# NeuroStimDuino.net
KiCad netlist of a schematic drawn in EAGLE
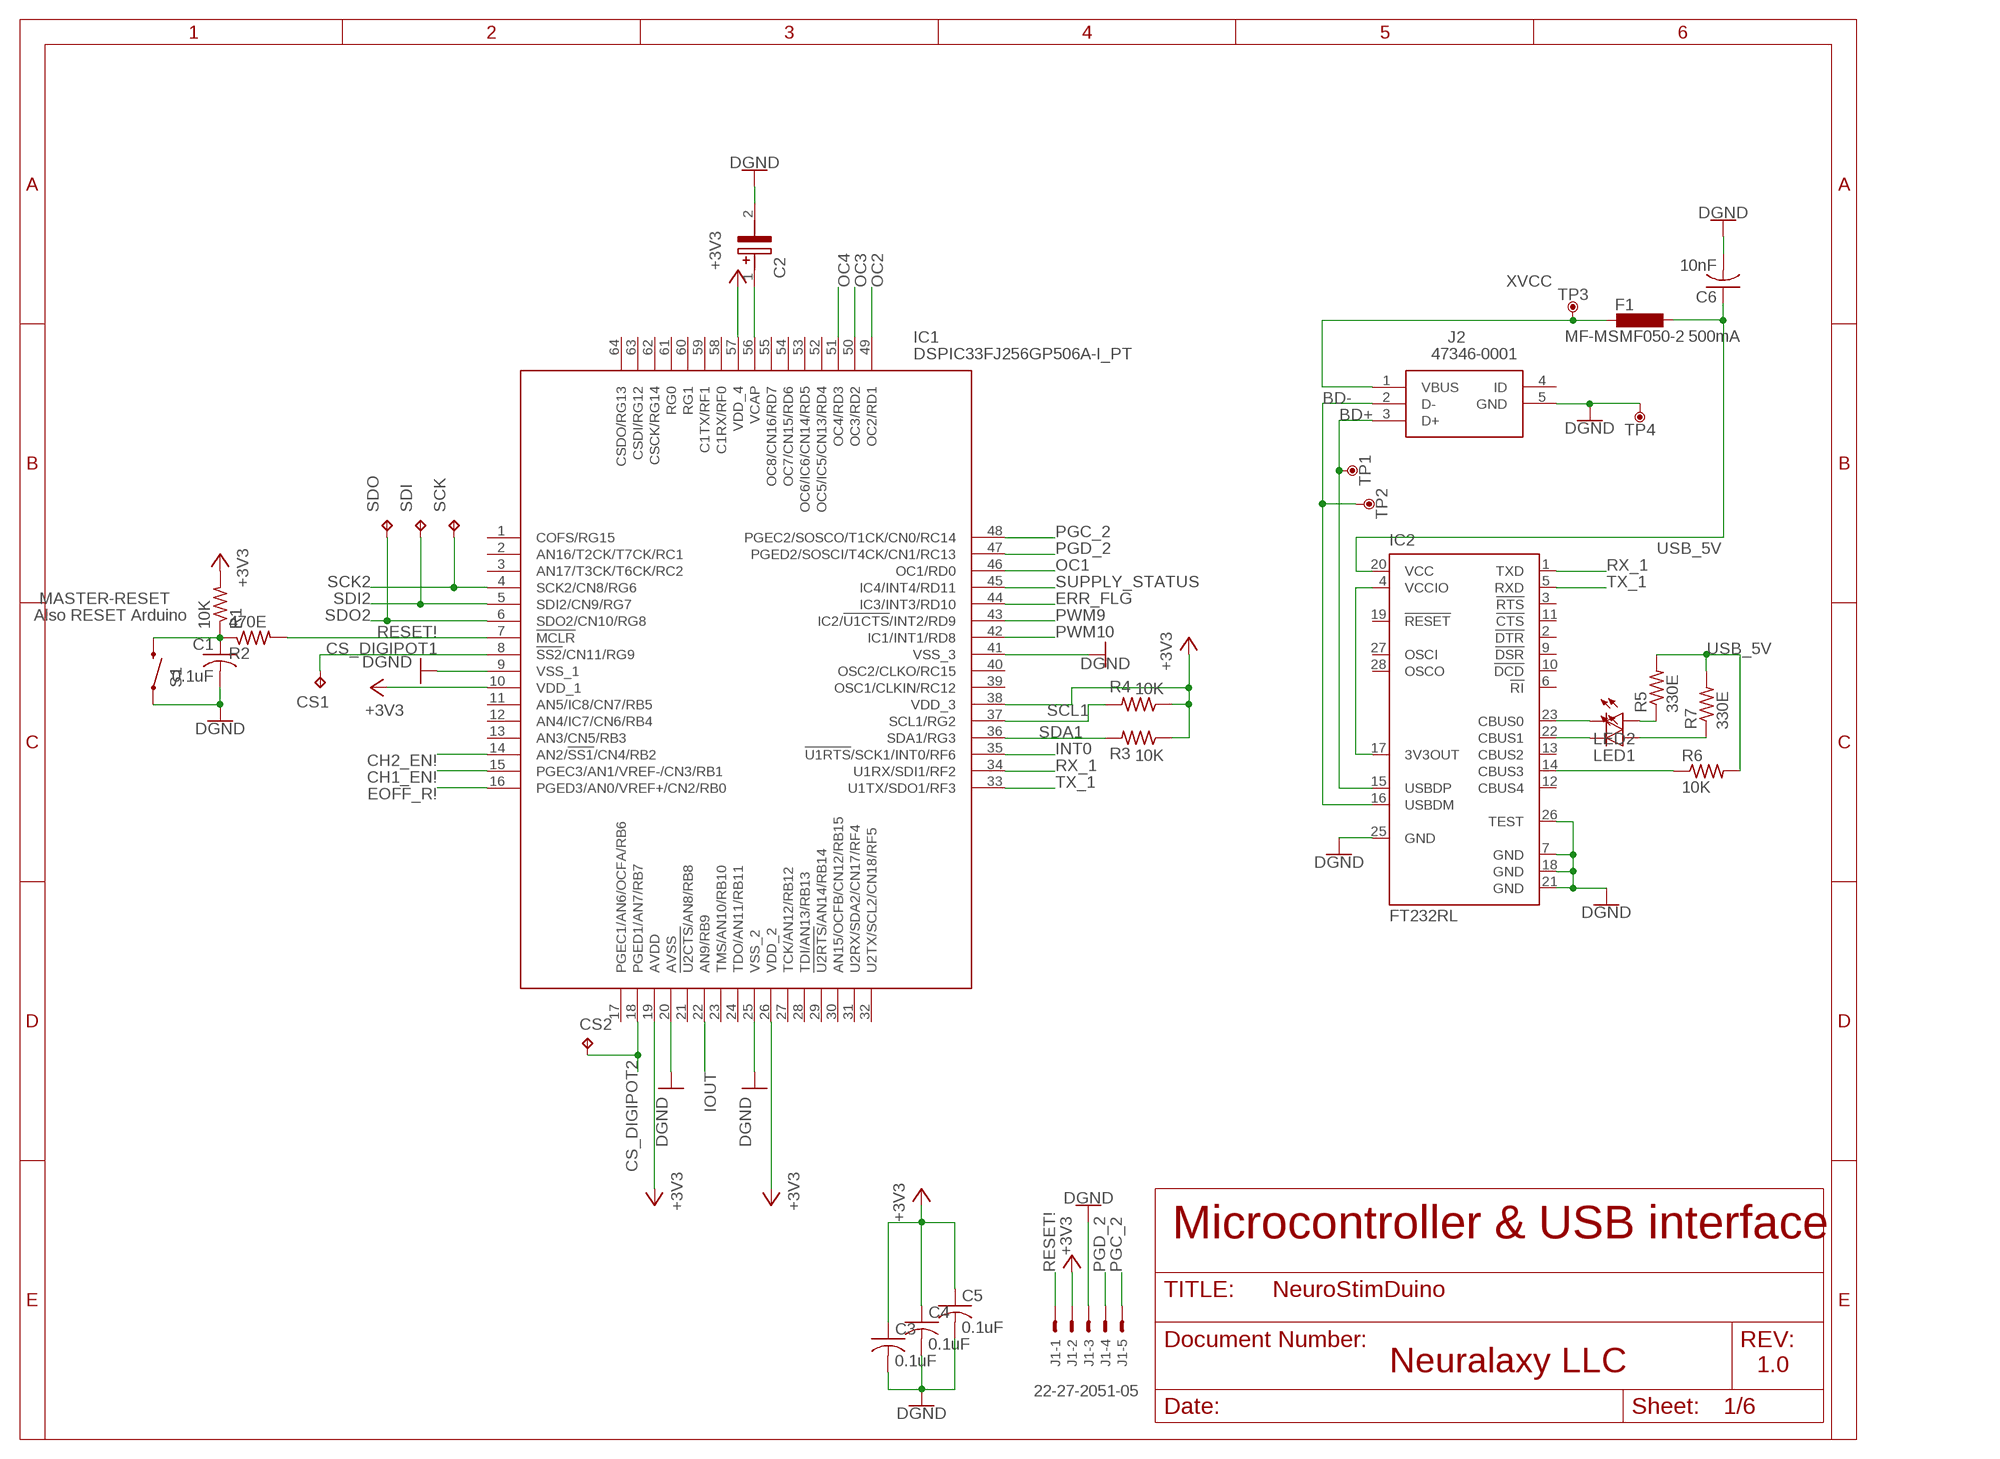
[diagram p0: schematic, sheet 1]
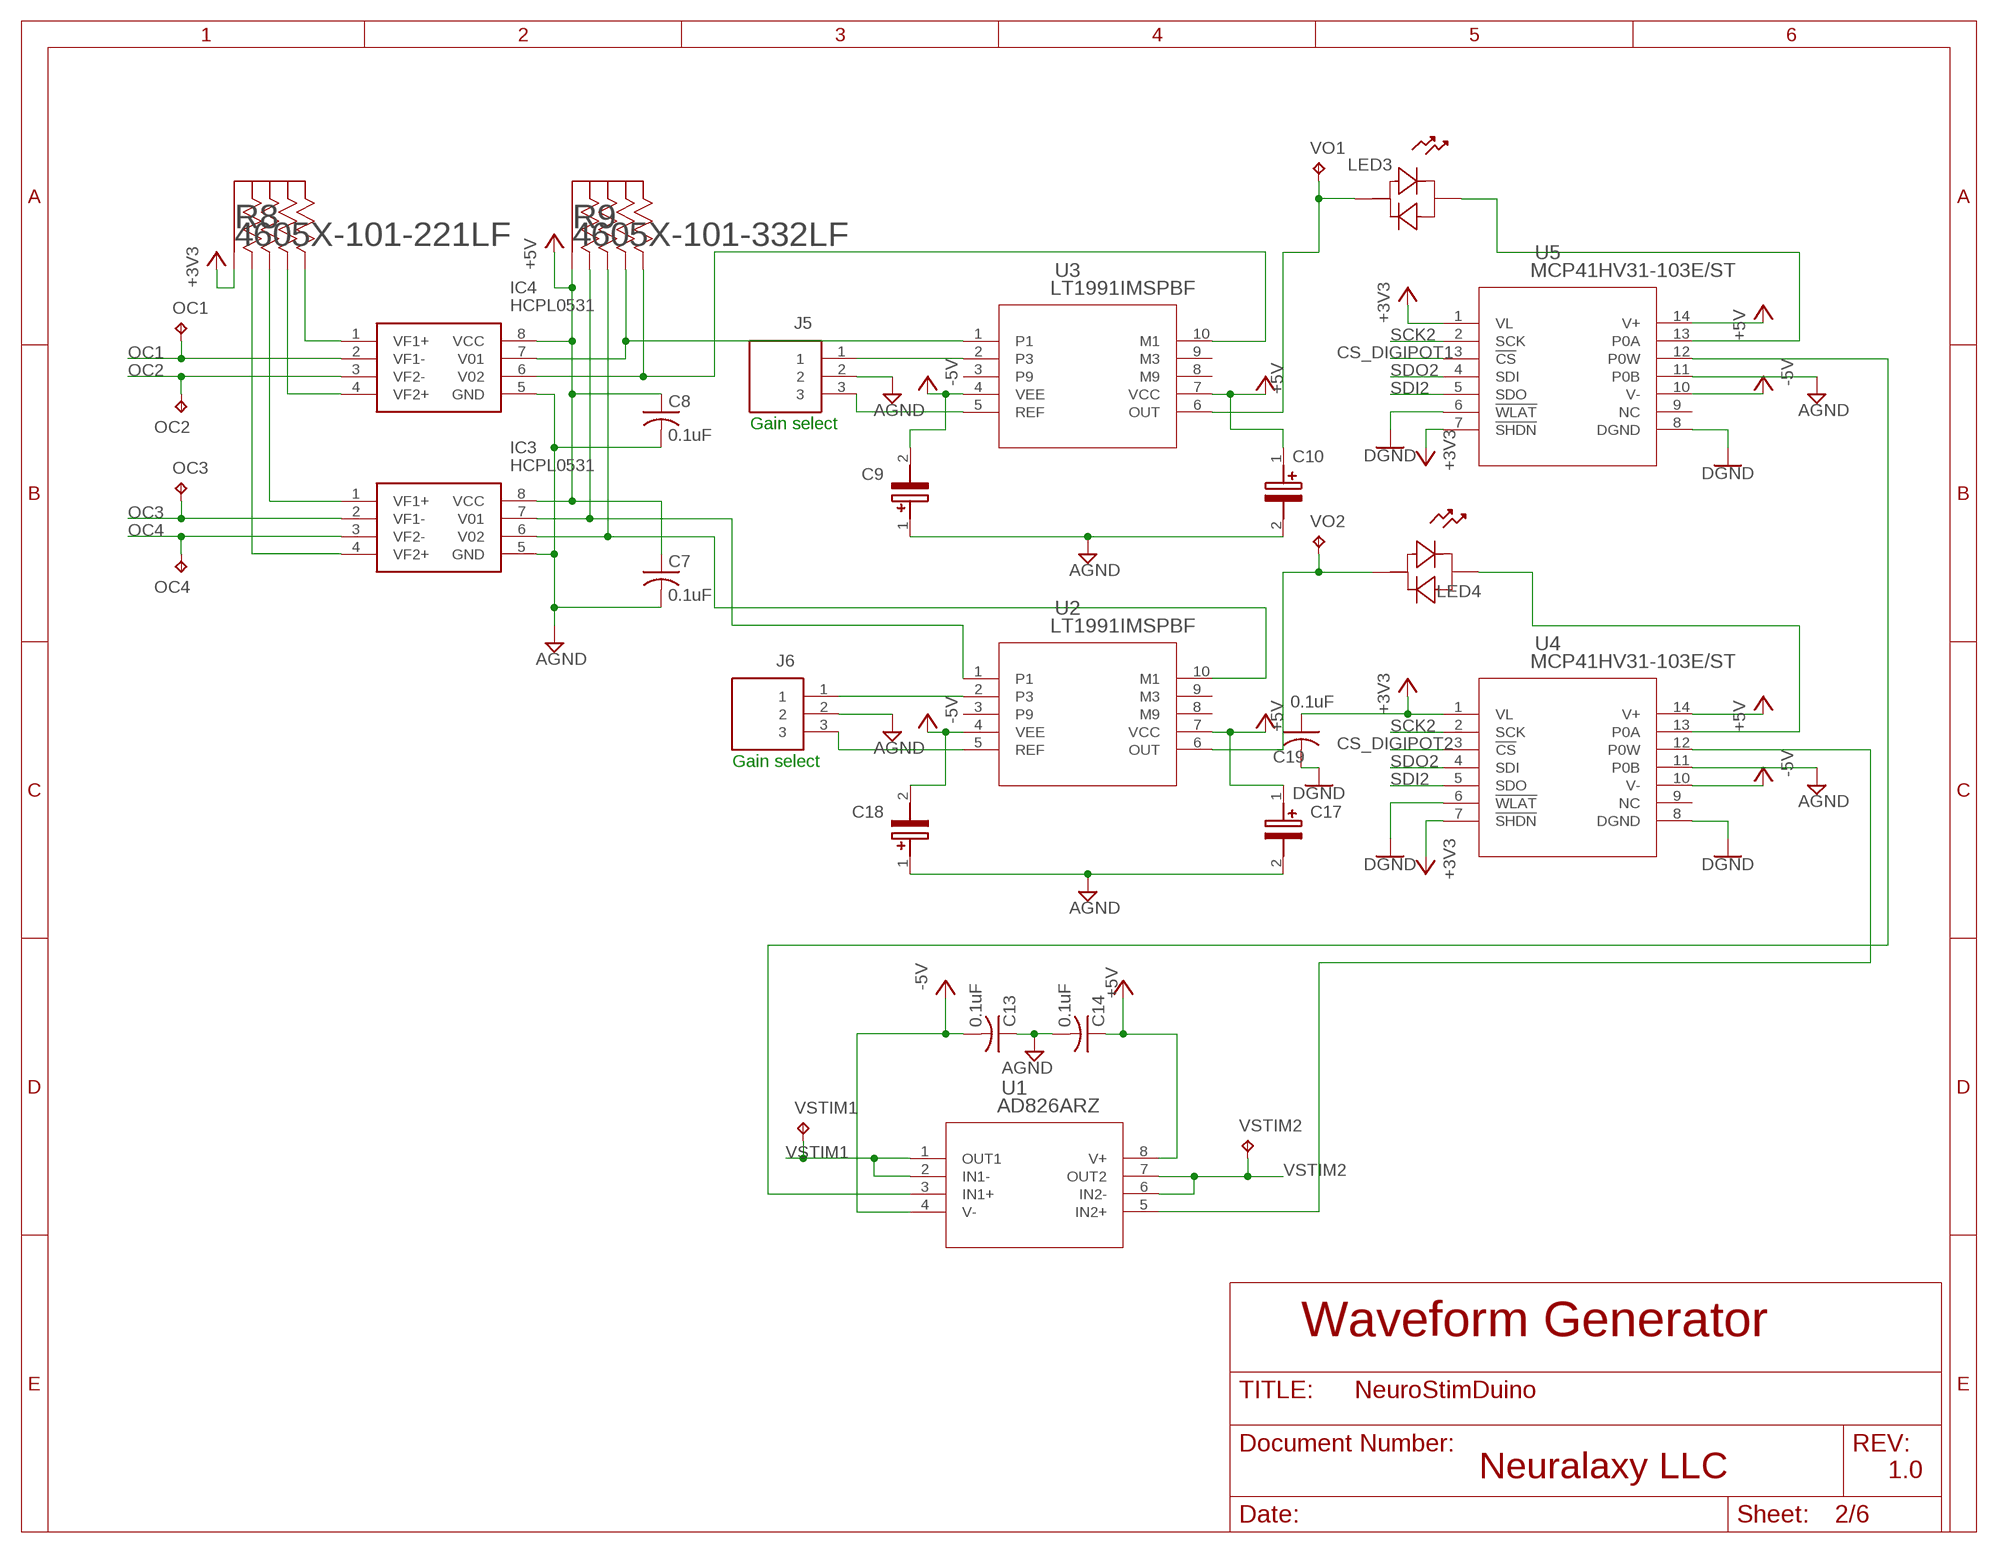
[diagram p1: schematic, sheet 2]
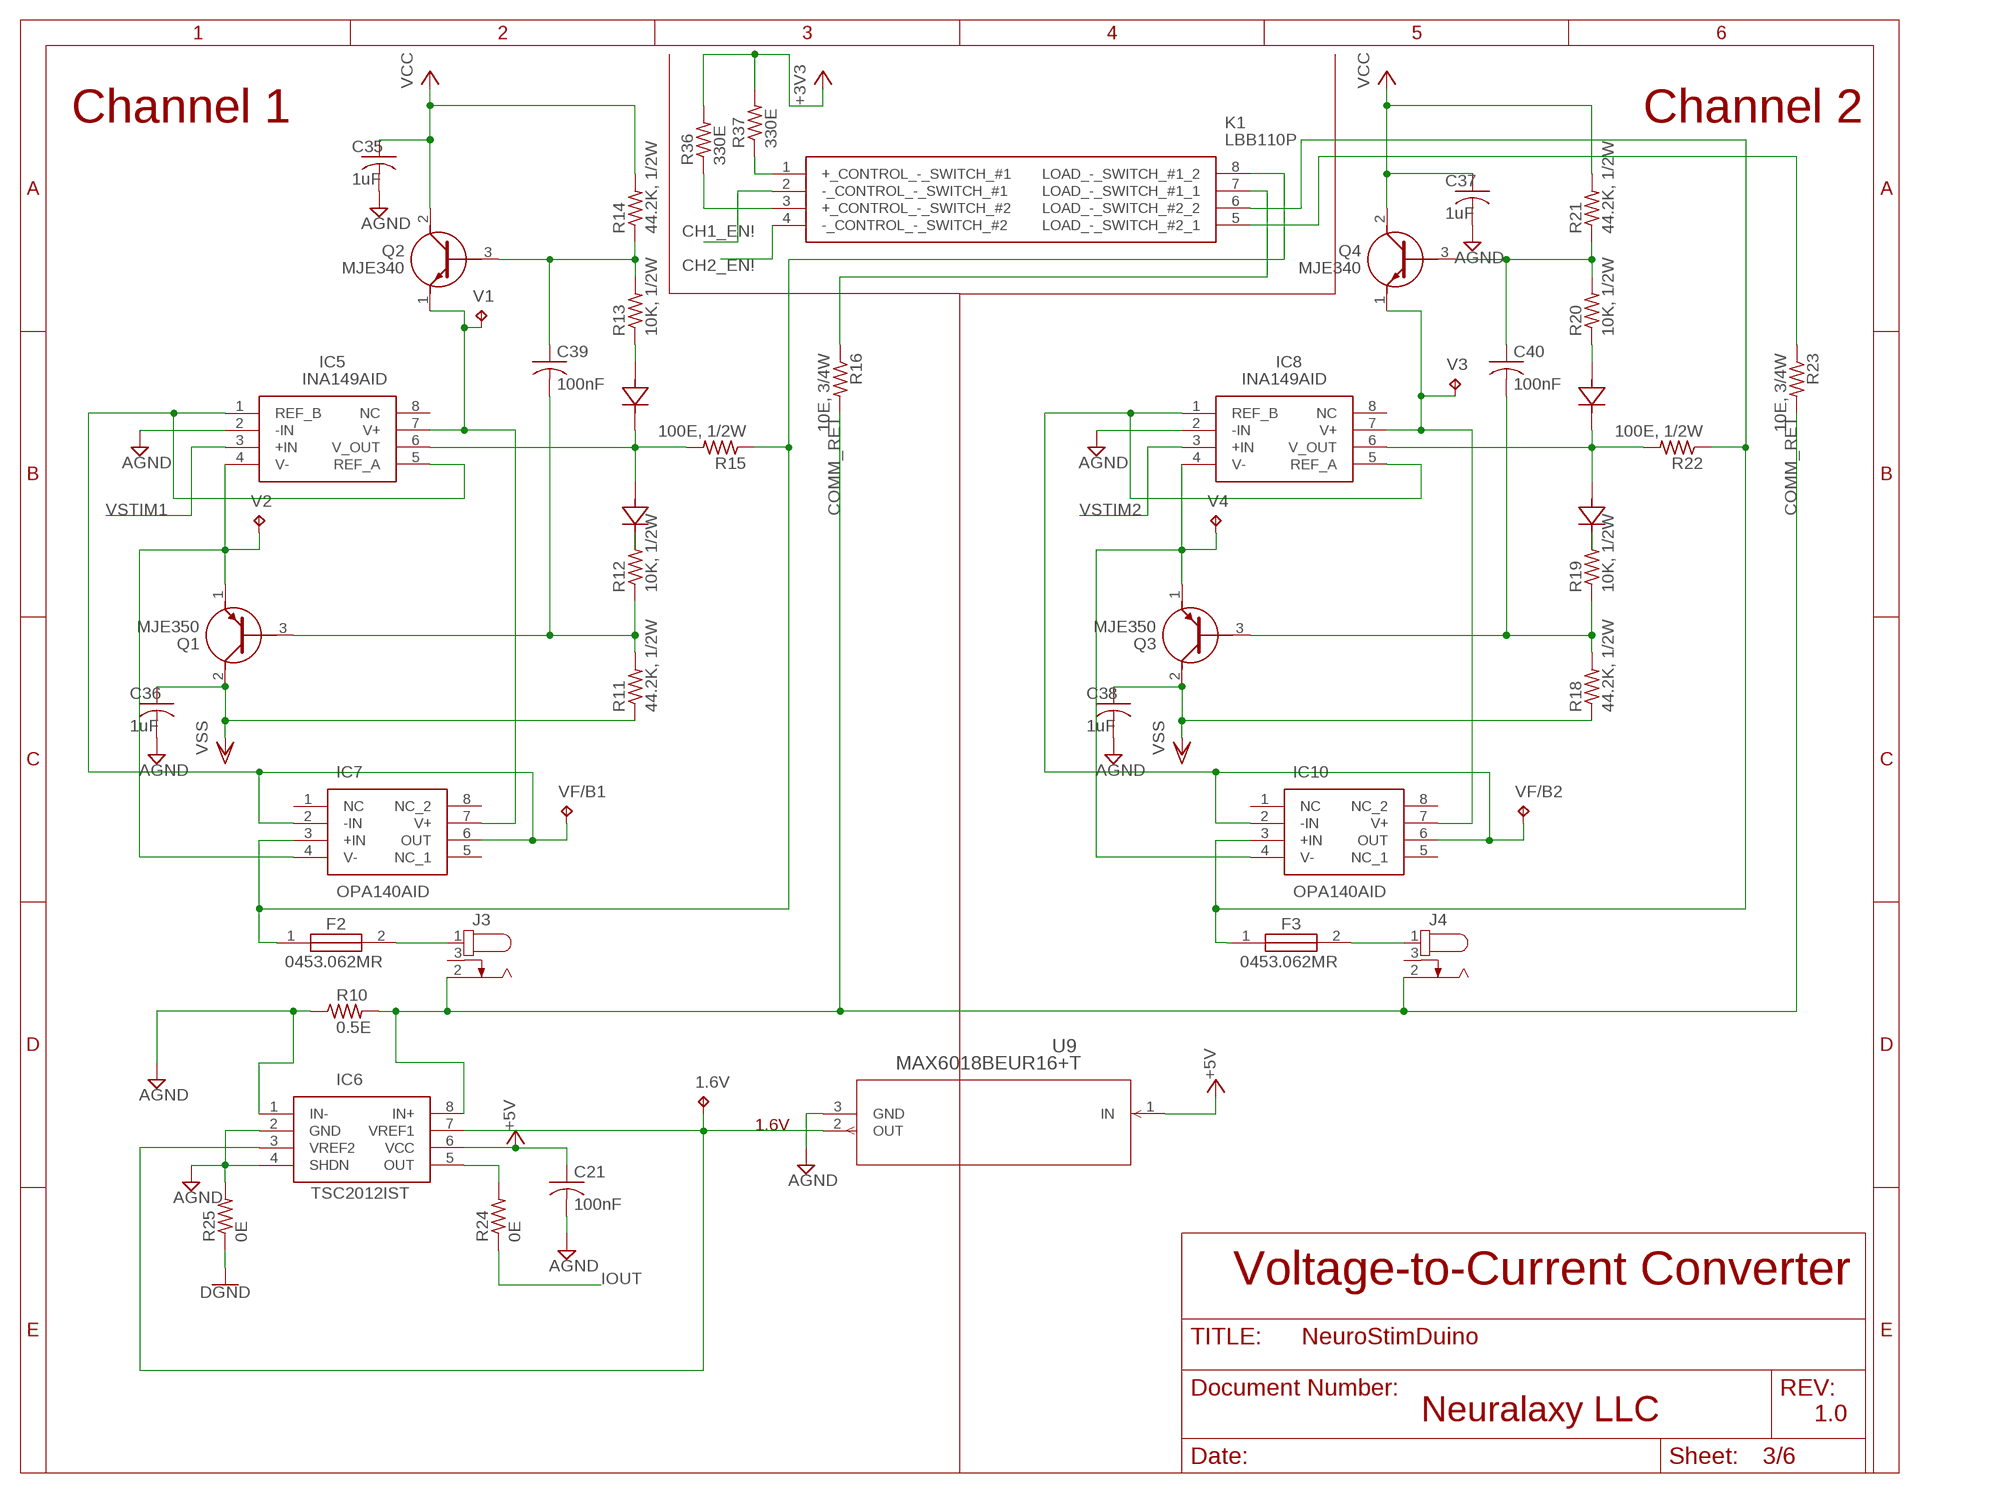
[diagram p2: schematic, sheet 3]
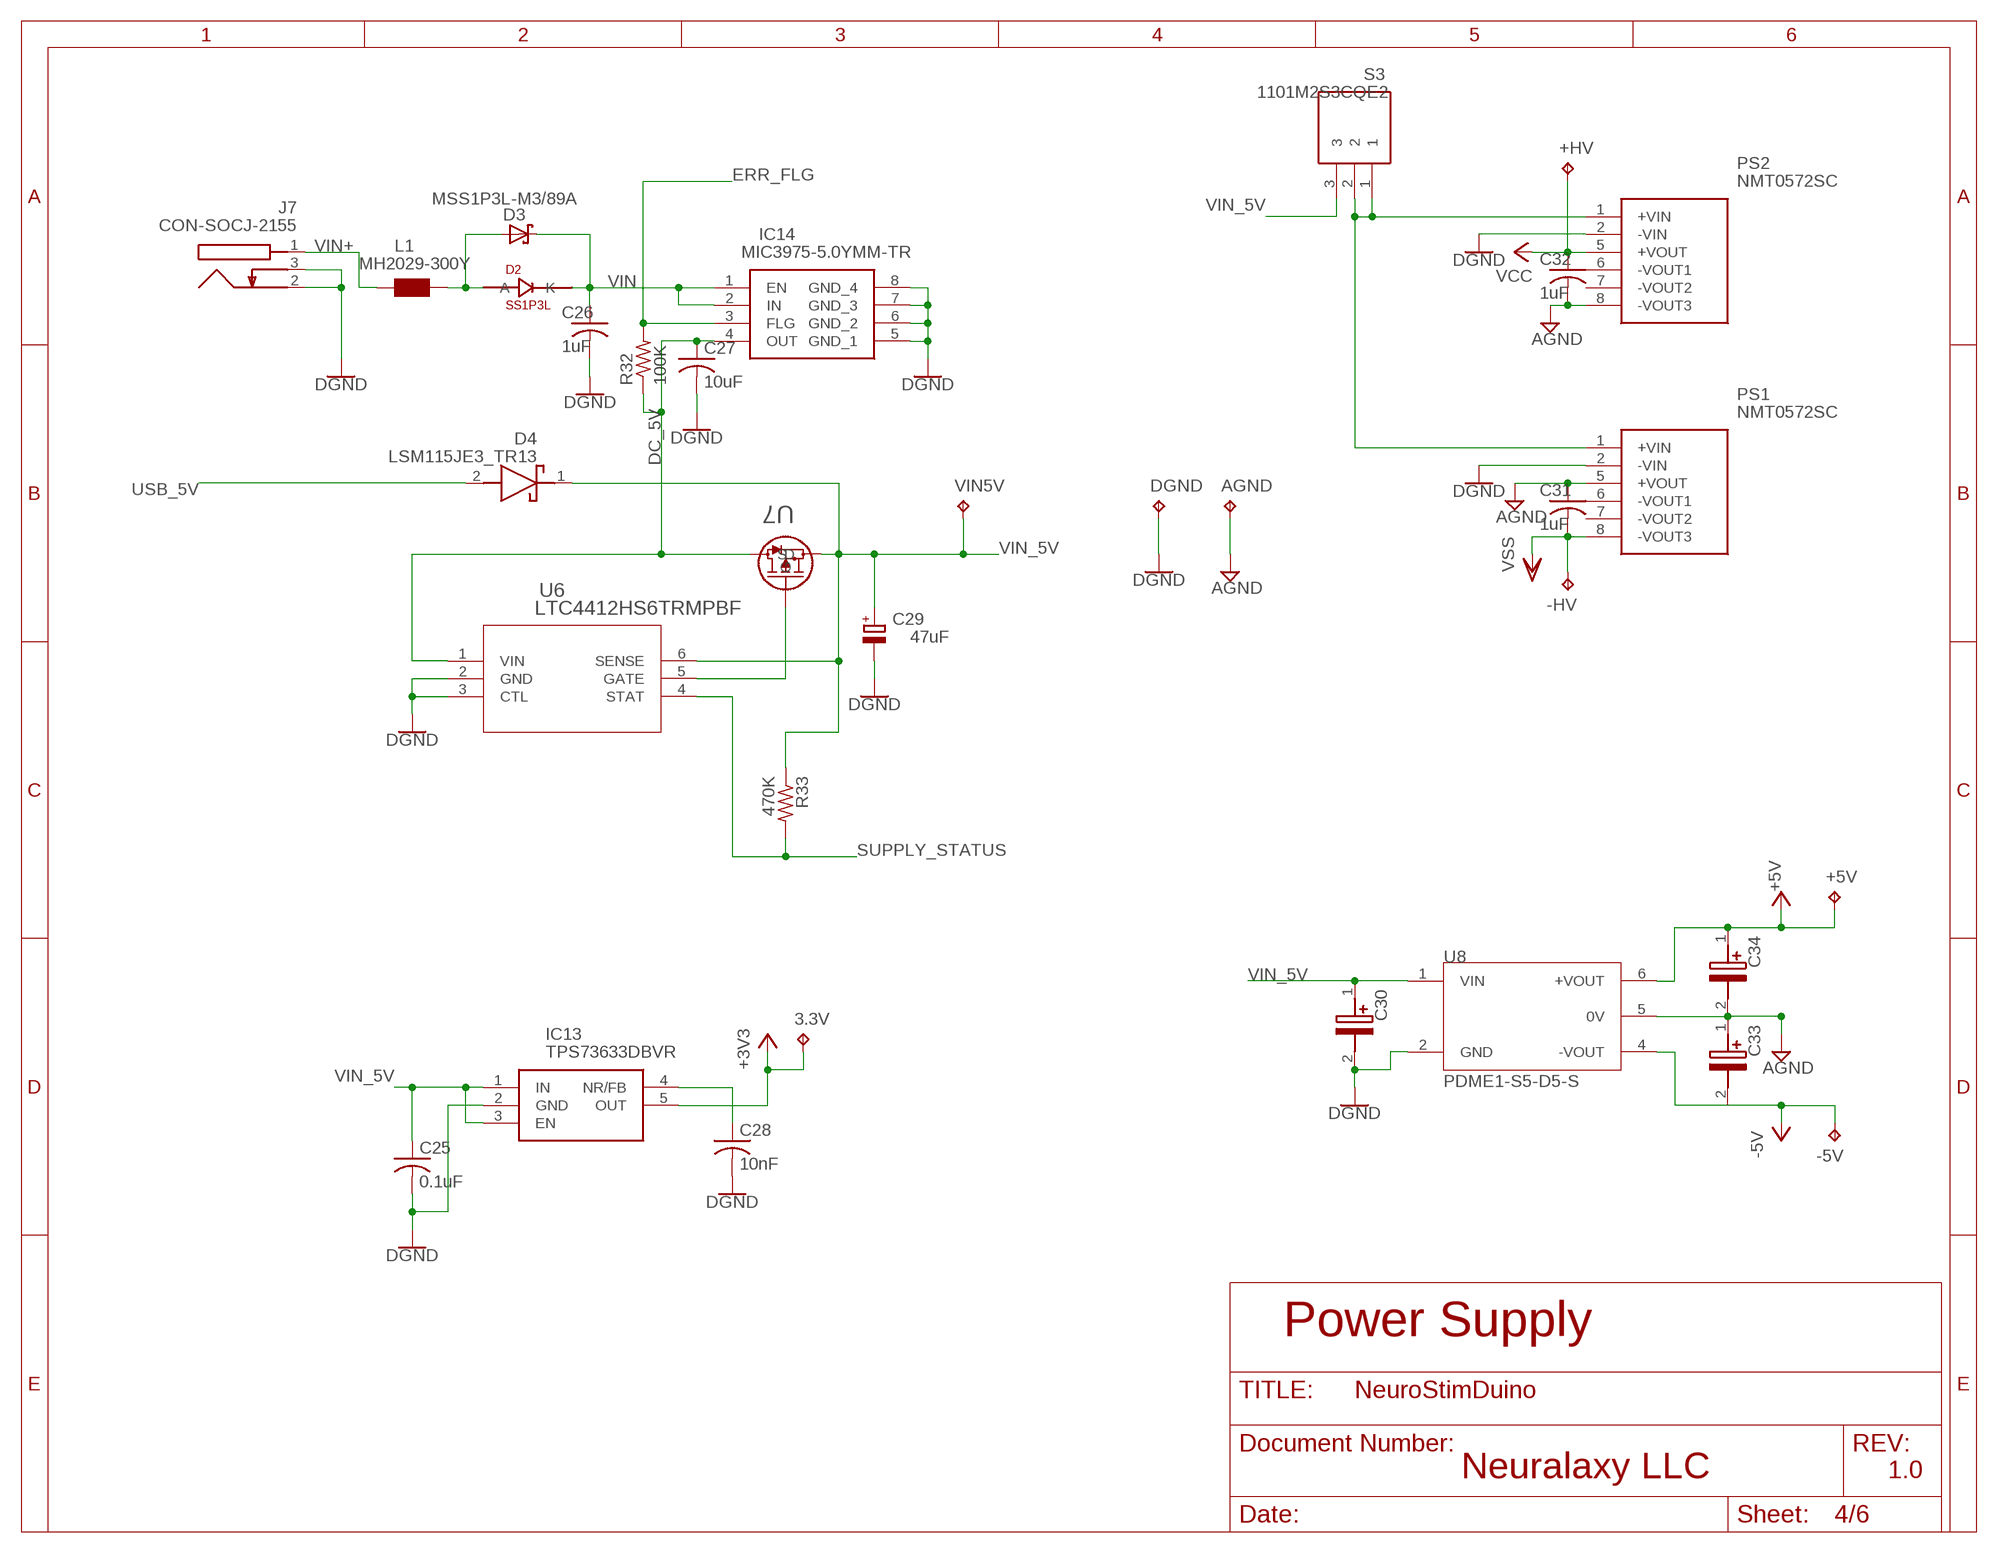
[diagram p3: schematic, sheet 4]
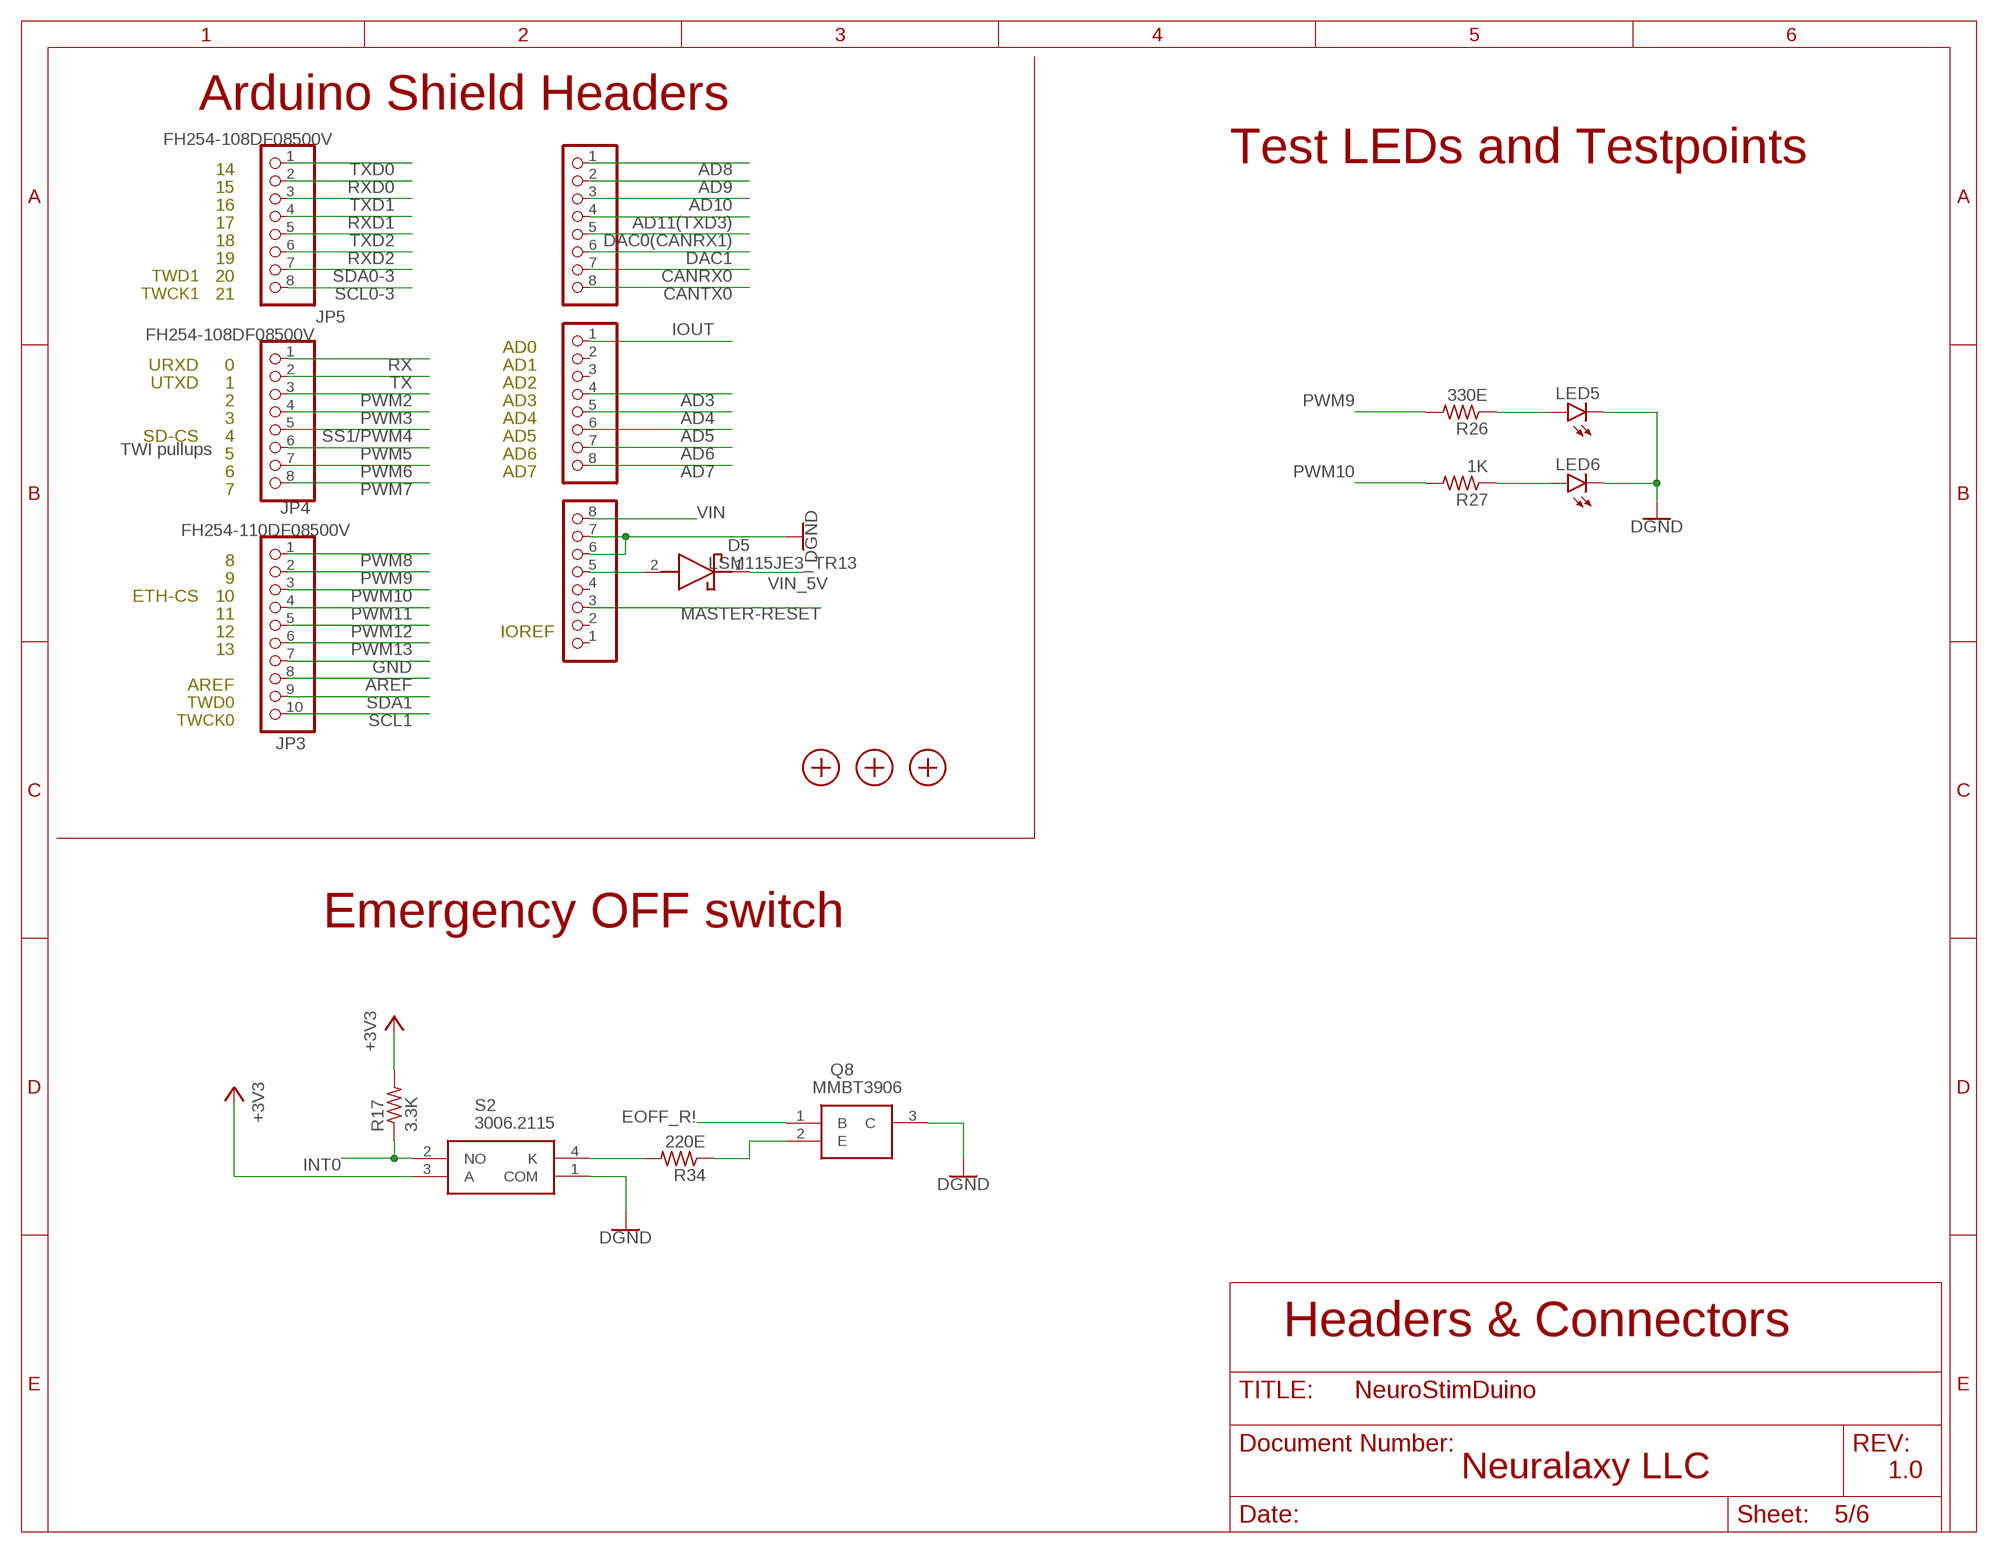
[diagram p4: schematic, sheet 5]
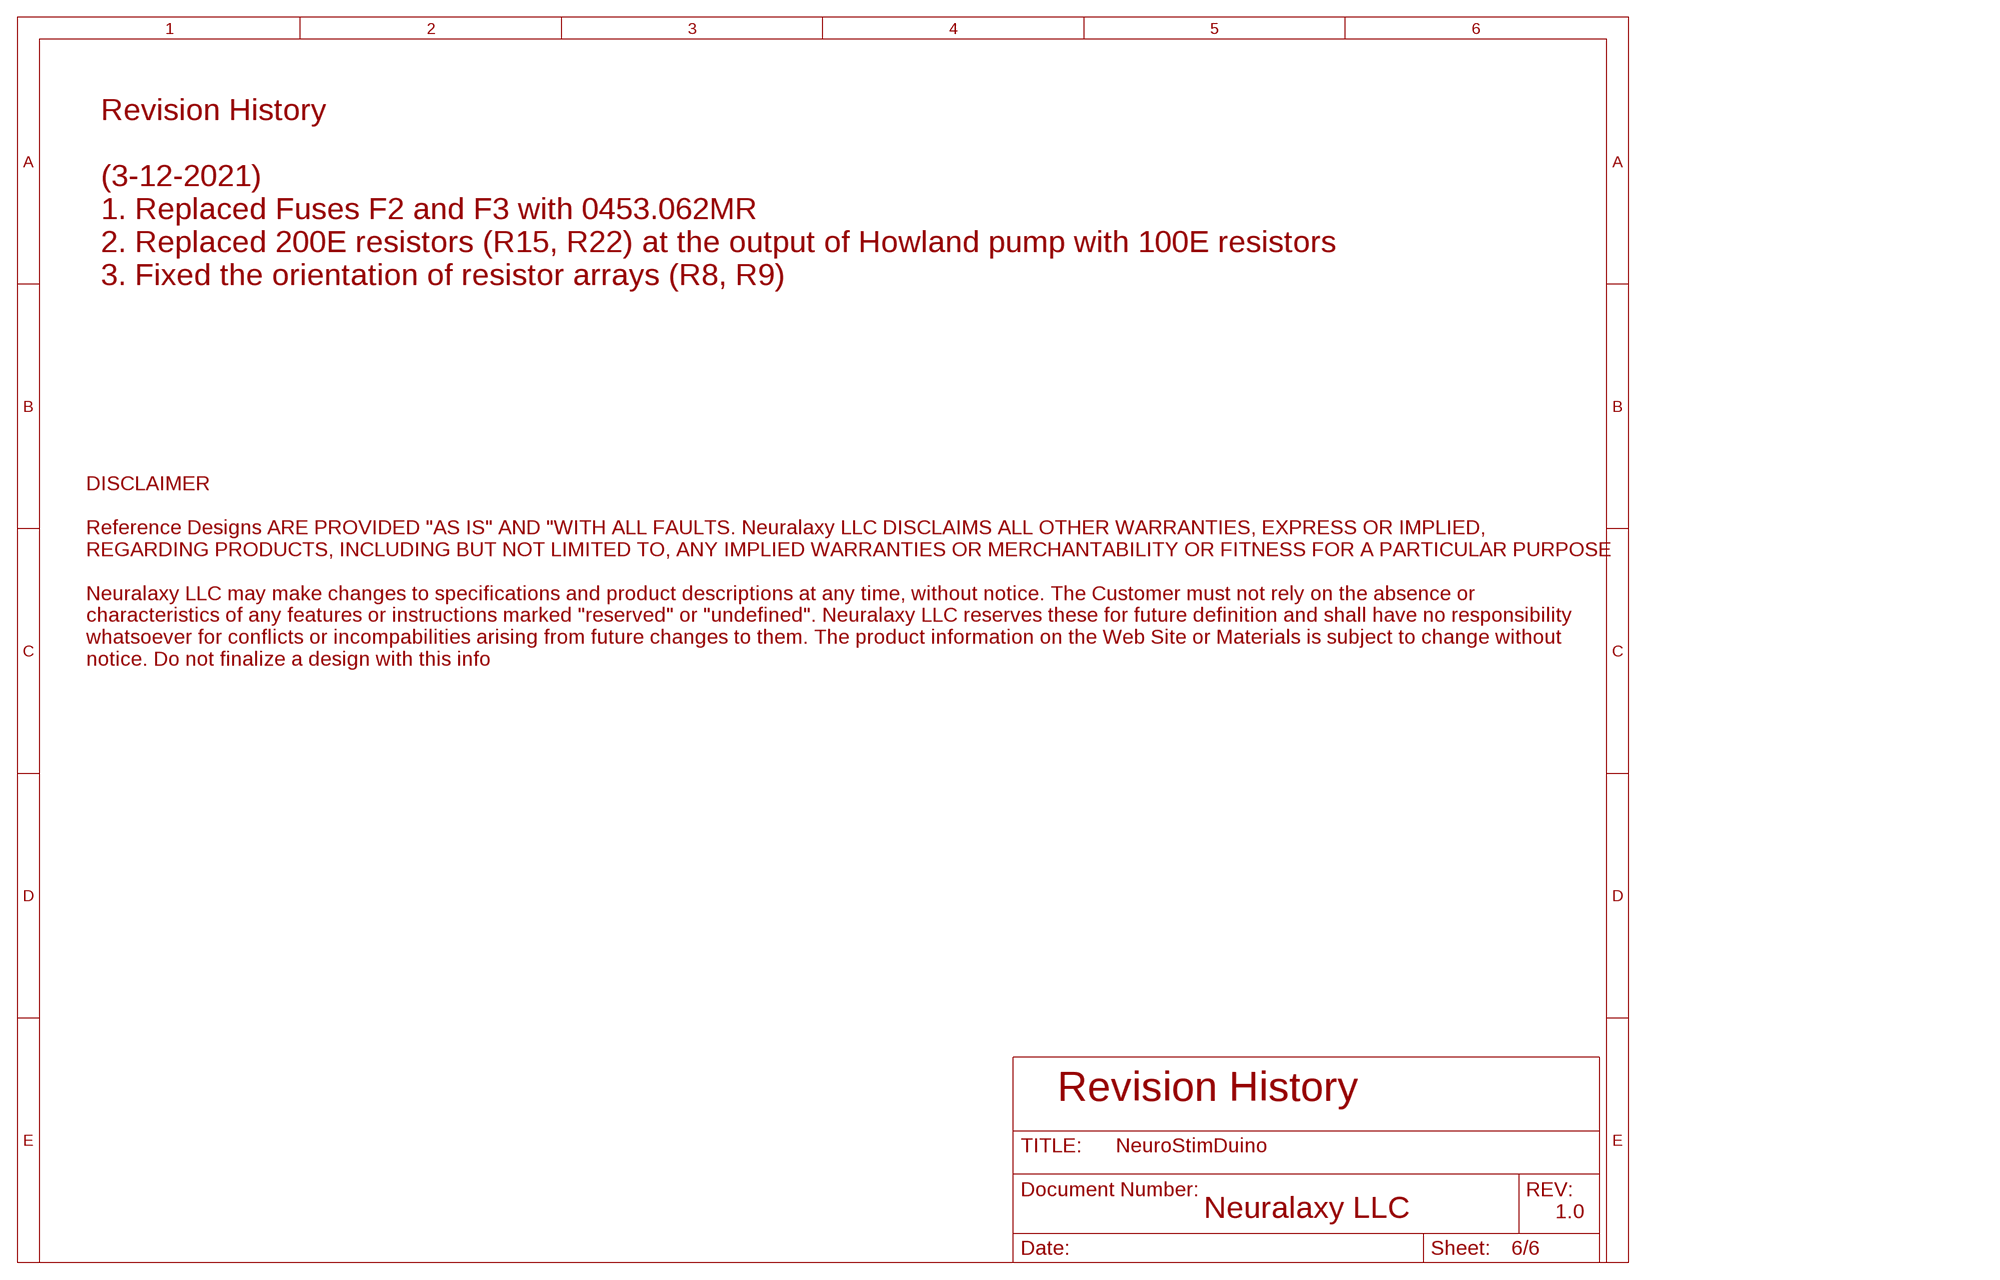
[diagram p5: schematic, sheet 6]

(export (version "E")
  (design (tool "Eeschema 10.0.6"))
  (components
    (comp (ref "D5")
      (value "LSM115JE3_TR13")
      (footprint "eagle-import:DIOM5436X330N")
      (fields
        (field (name "ARROW_PART_NUMBER") "LSM115JE3/TR13")
        (field (name "MOUSER_PART_NUMBER") "494-LSM115JE3/TR13")
      )
      (libsource (lib "eagle-import") (part "LSM115JE3_TR13"))
    )
    (comp (ref "JP3")
      (value "FH254-110DF08500V")
      (footprint "eagle-import:1X10")
      (fields (field (name "PART_NUMBER") "20TW-537"))
      (libsource (lib "eagle-import") (part "1684_20TW-537"))
    )
    (comp (ref "JP4")
      (value "FH254-108DF08500V")
      (footprint "eagle-import:1X08")
      (fields (field (name "PART_NUMBER") "20TW-536"))
      (libsource (lib "eagle-import") (part "1683_20TW-536"))
    )
    (comp (ref "JP5")
      (value "FH254-108DF08500V")
      (footprint "eagle-import:1X08")
      (fields (field (name "PART_NUMBER") "20TW-536"))
      (libsource (lib "eagle-import") (part "1683_20TW-536"))
    )
    (comp (ref "JP6")
      (value "FH254-108DF08500V")
      (footprint "eagle-import:1X08")
      (fields (field (name "PART_NUMBER") "20TW-536"))
      (libsource (lib "eagle-import") (part "1683_20TW-536"))
    )
    (comp (ref "JP7")
      (value "FH254-108DF08500V")
      (footprint "eagle-import:1X08")
      (fields (field (name "PART_NUMBER") "20TW-536"))
      (libsource (lib "eagle-import") (part "1683_20TW-536"))
    )
    (comp (ref "JP8")
      (value "FH254-108DF08500V")
      (footprint "eagle-import:1X08")
      (fields (field (name "PART_NUMBER") "20TW-536"))
      (libsource (lib "eagle-import") (part "1683_20TW-536"))
    )
    (comp (ref "LED5")
      (value "LEDCHIPLED_1206")
      (footprint "eagle-import:CHIPLED_1206")
      (libsource (lib "eagle-import") (part "LEDCHIPLED_1206"))
    )
    (comp (ref "LED6")
      (value "LEDCHIPLED_1206")
      (footprint "eagle-import:CHIPLED_1206")
      (libsource (lib "eagle-import") (part "LEDCHIPLED_1206"))
    )
    (comp (ref "Q8")
      (value "MMBT3906")
      (footprint "eagle-import:SOT95P240X120-3N")
      (fields (field (name "MOUSER_PART_NUMBER") "512-MMBT3906"))
      (libsource (lib "eagle-import") (part "MMBT3906"))
    )
    (comp (ref "R17")
      (value "3.3K")
      (footprint "eagle-import:R1206")
      (libsource (lib "eagle-import") (part "rcl_334_R-US_R1206"))
    )
    (comp (ref "R26")
      (value "330E")
      (footprint "eagle-import:R0603")
      (libsource (lib "eagle-import") (part "R-US_R0603"))
    )
    (comp (ref "R27")
      (value "1K")
      (footprint "eagle-import:R0603")
      (libsource (lib "eagle-import") (part "R-US_R0603"))
    )
    (comp (ref "R34")
      (value "220E")
      (footprint "eagle-import:R1206")
      (libsource (lib "eagle-import") (part "rcl_334_R-US_R1206"))
    )
    (comp (ref "S2")
      (value "3006.2115")
      (footprint "eagle-import:30062115")
      (fields (field (name "MOUSER_PART_NUMBER") "979-3006.2115"))
      (libsource (lib "eagle-import") (part "3006.2115"))
    )
    (comp (ref "U$1")
      (value "FIDUCIALMOUNT")
      (footprint "eagle-import:FIDUCIA-MOUNT")
      (libsource (lib "eagle-import") (part "FIDUCIALMOUNT"))
    )
    (comp (ref "U$2")
      (value "FIDUCIALMOUNT")
      (footprint "eagle-import:FIDUCIA-MOUNT")
      (libsource (lib "eagle-import") (part "FIDUCIALMOUNT"))
    )
    (comp (ref "U$3")
      (value "FIDUCIALMOUNT")
      (footprint "eagle-import:FIDUCIA-MOUNT")
      (libsource (lib "eagle-import") (part "FIDUCIALMOUNT"))
    )
    (comp (ref "1.6V")
      (value "TPTP10R")
      (footprint "eagle-import:TP10R")
      (libsource (lib "eagle-import") (part "TPTP10R"))
    )
    (comp (ref "C21")
      (value "100nF")
      (footprint "eagle-import:C1206")
      (libsource (lib "eagle-import") (part "rcl_334_C-USC1206"))
    )
    (comp (ref "C35")
      (value "1uF")
      (footprint "eagle-import:C0805")
      (libsource (lib "eagle-import") (part "rcl_334_C-USC0805"))
    )
    (comp (ref "C36")
      (value "1uF")
      (footprint "eagle-import:C0805")
      (libsource (lib "eagle-import") (part "rcl_334_C-USC0805"))
    )
    (comp (ref "C37")
      (value "1uF")
      (footprint "eagle-import:C0805")
      (libsource (lib "eagle-import") (part "rcl_334_C-USC0805"))
    )
    (comp (ref "C38")
      (value "1uF")
      (footprint "eagle-import:C0805")
      (libsource (lib "eagle-import") (part "rcl_334_C-USC0805"))
    )
    (comp (ref "C39")
      (value "100nF")
      (footprint "eagle-import:C0805K")
      (libsource (lib "eagle-import") (part "rcl_334_C-USC0805K"))
    )
    (comp (ref "C40")
      (value "100nF")
      (footprint "eagle-import:C0805K")
      (libsource (lib "eagle-import") (part "rcl_334_C-USC0805K"))
    )
    (comp (ref "D6")
      (value "GF1J-E3DO-214BA-L")
      (footprint "eagle-import:DO-214BA-L")
      (fields (field (name "MANUFACTURER_PART_NUMBER") "GF1J-E3"))
      (libsource (lib "eagle-import") (part "GF1J-E3DO-214BA-L"))
    )
    (comp (ref "D7")
      (value "GF1J-E3DO-214BA-L")
      (footprint "eagle-import:DO-214BA-L")
      (fields (field (name "MANUFACTURER_PART_NUMBER") "GF1J-E3"))
      (libsource (lib "eagle-import") (part "GF1J-E3DO-214BA-L"))
    )
    (comp (ref "D8")
      (value "GF1J-E3DO-214BA-L")
      (footprint "eagle-import:DO-214BA-L")
      (fields (field (name "MANUFACTURER_PART_NUMBER") "GF1J-E3"))
      (libsource (lib "eagle-import") (part "GF1J-E3DO-214BA-L"))
    )
    (comp (ref "D9")
      (value "GF1J-E3DO-214BA-L")
      (footprint "eagle-import:DO-214BA-L")
      (fields (field (name "MANUFACTURER_PART_NUMBER") "GF1J-E3"))
      (libsource (lib "eagle-import") (part "GF1J-E3DO-214BA-L"))
    )
    (comp (ref "F2")
      (value "0453.062MR")
      (footprint "eagle-import:FUSC6127X294N")
      (libsource (lib "eagle-import") (part "0453.062MR"))
    )
    (comp (ref "F3")
      (value "0453.062MR")
      (footprint "eagle-import:FUSC6127X294N")
      (libsource (lib "eagle-import") (part "0453.062MR"))
    )
    (comp (ref "IC5")
      (value "INA149AID")
      (footprint "eagle-import:SOIC127P600X175-8N")
      (fields (field (name "MOUSER_PART_NUMBER") "595-INA149AID"))
      (libsource (lib "eagle-import") (part "INA149AID"))
    )
    (comp (ref "IC6")
      (value "TSC2011IDT")
      (footprint "eagle-import:SOP65P490X110-8N")
      (fields
        (field (name "MANUFACTURER_PART_NUMBER") "TSC2011IST")
        (field (name "MOUSER_PART_NUMBER") "511-TSC2011IST")
      )
      (libsource (lib "eagle-import") (part "TSC2011IDT"))
    )
    (comp (ref "IC7")
      (value "OPA140AID")
      (footprint "eagle-import:SOIC127P600X175-8N")
      (fields (field (name "MOUSER_PART_NUMBER") "595-OPA140AID"))
      (libsource (lib "eagle-import") (part "OPA140AID"))
    )
    (comp (ref "IC8")
      (value "INA149AID")
      (footprint "eagle-import:SOIC127P600X175-8N")
      (fields (field (name "MOUSER_PART_NUMBER") "595-INA149AID"))
      (libsource (lib "eagle-import") (part "INA149AID"))
    )
    (comp (ref "IC10")
      (value "OPA140AID")
      (footprint "eagle-import:SOIC127P600X175-8N")
      (fields (field (name "MOUSER_PART_NUMBER") "595-OPA140AID"))
      (libsource (lib "eagle-import") (part "OPA140AID"))
    )
    (comp (ref "J3")
      (value "694101308002")
      (footprint "eagle-import:694101308002")
      (libsource (lib "eagle-import") (part "694101308002"))
    )
    (comp (ref "J4")
      (value "694101308002")
      (footprint "eagle-import:694101308002")
      (libsource (lib "eagle-import") (part "694101308002"))
    )
    (comp (ref "K1")
      (value "LBB110P")
      (footprint "eagle-import:SOP254P940X229-8N")
      (fields (field (name "MOUSER_PART_NUMBER") "849-LBB110P"))
      (libsource (lib "eagle-import") (part "LBB110P"))
    )
    (comp (ref "Q1")
      (value "MJE350")
      (footprint "eagle-import:TO229P300X760X1364-3P")
      (fields
        (field (name "MANUFACTURER_PART_NUMBER") "MJE350G")
        (field (name "MOUSER_PART_NUMBER") "863-MJE350G")
      )
      (libsource (lib "eagle-import") (part "MJE350"))
    )
    (comp (ref "Q2")
      (value "MJE340")
      (footprint "eagle-import:TO229P290X760X1320-3P")
      (fields (field (name "MOUSER_PART_NUMBER") "511-MJE340"))
      (libsource (lib "eagle-import") (part "MJE340"))
    )
    (comp (ref "Q3")
      (value "MJE350")
      (footprint "eagle-import:TO229P300X760X1364-3P")
      (fields
        (field (name "MANUFACTURER_PART_NUMBER") "MJE350G")
        (field (name "MOUSER_PART_NUMBER") "863-MJE350G")
      )
      (libsource (lib "eagle-import") (part "MJE350"))
    )
    (comp (ref "Q4")
      (value "MJE340")
      (footprint "eagle-import:TO229P290X760X1320-3P")
      (fields (field (name "MOUSER_PART_NUMBER") "511-MJE340"))
      (libsource (lib "eagle-import") (part "MJE340"))
    )
    (comp (ref "R10")
      (value "0.5E")
      (footprint "eagle-import:R1206")
      (libsource (lib "eagle-import") (part "rcl_334_R-US_R1206"))
    )
    (comp (ref "R11")
      (value "44.2K, 1/2W")
      (footprint "eagle-import:R1206")
      (libsource (lib "eagle-import") (part "rcl_334_R-US_R1206"))
    )
    (comp (ref "R12")
      (value "10K, 1/2W")
      (footprint "eagle-import:R1206")
      (libsource (lib "eagle-import") (part "rcl_334_R-US_R1206"))
    )
    (comp (ref "R13")
      (value "10K, 1/2W")
      (footprint "eagle-import:R1206")
      (libsource (lib "eagle-import") (part "rcl_334_R-US_R1206"))
    )
    (comp (ref "R14")
      (value "44.2K, 1/2W")
      (footprint "eagle-import:R1206")
      (libsource (lib "eagle-import") (part "rcl_334_R-US_R1206"))
    )
    (comp (ref "R15")
      (value "100E, 1/2W")
      (footprint "eagle-import:R1206")
      (libsource (lib "eagle-import") (part "rcl_334_R-US_R1206"))
    )
    (comp (ref "R16")
      (value "10E, 3/4W")
      (footprint "eagle-import:R1206")
      (libsource (lib "eagle-import") (part "rcl_334_R-US_R1206"))
    )
    (comp (ref "R18")
      (value "44.2K, 1/2W")
      (footprint "eagle-import:R1206")
      (libsource (lib "eagle-import") (part "rcl_334_R-US_R1206"))
    )
    (comp (ref "R19")
      (value "10K, 1/2W")
      (footprint "eagle-import:R1206")
      (libsource (lib "eagle-import") (part "rcl_334_R-US_R1206"))
    )
    (comp (ref "R20")
      (value "10K, 1/2W")
      (footprint "eagle-import:R1206")
      (libsource (lib "eagle-import") (part "rcl_334_R-US_R1206"))
    )
    (comp (ref "R21")
      (value "44.2K, 1/2W")
      (footprint "eagle-import:R1206")
      (libsource (lib "eagle-import") (part "rcl_334_R-US_R1206"))
    )
    (comp (ref "R22")
      (value "100E, 1/2W")
      (footprint "eagle-import:R1206")
      (libsource (lib "eagle-import") (part "rcl_334_R-US_R1206"))
    )
    (comp (ref "R23")
      (value "10E, 3/4W")
      (footprint "eagle-import:R1206")
      (libsource (lib "eagle-import") (part "rcl_334_R-US_R1206"))
    )
    (comp (ref "R24")
      (value "0E")
      (footprint "eagle-import:R1206")
      (libsource (lib "eagle-import") (part "rcl_334_R-US_R1206"))
    )
    (comp (ref "R25")
      (value "0E")
      (footprint "eagle-import:R1206")
      (libsource (lib "eagle-import") (part "rcl_334_R-US_R1206"))
    )
    (comp (ref "R36")
      (value "330E")
      (footprint "eagle-import:R1206")
      (libsource (lib "eagle-import") (part "R-US_R1206"))
    )
    (comp (ref "R37")
      (value "330E")
      (footprint "eagle-import:R1206")
      (libsource (lib "eagle-import") (part "R-US_R1206"))
    )
    (comp (ref "U9")
      (value "MAX6018BEUR16+T")
      (footprint "eagle-import:21-0051H_MXM")
      (libsource (lib "eagle-import") (part "MAX6018BEUR16+T"))
    )
    (comp (ref "V1")
      (value "TPTP10R")
      (footprint "eagle-import:TP10R")
      (libsource (lib "eagle-import") (part "TPTP10R"))
    )
    (comp (ref "V2")
      (value "TPTP10R")
      (footprint "eagle-import:TP10R")
      (libsource (lib "eagle-import") (part "TPTP10R"))
    )
    (comp (ref "V3")
      (value "TPTP10R")
      (footprint "eagle-import:TP10R")
      (libsource (lib "eagle-import") (part "TPTP10R"))
    )
    (comp (ref "V4")
      (value "TPTP10R")
      (footprint "eagle-import:TP10R")
      (libsource (lib "eagle-import") (part "TPTP10R"))
    )
    (comp (ref "VF/B1")
      (value "TPTP10R")
      (footprint "eagle-import:TP10R")
      (libsource (lib "eagle-import") (part "TPTP10R"))
    )
    (comp (ref "VF/B2")
      (value "TPTP10R")
      (footprint "eagle-import:TP10R")
      (libsource (lib "eagle-import") (part "TPTP10R"))
    )
    (comp (ref "C7")
      (value "0.1uF")
      (footprint "eagle-import:C1206")
      (libsource (lib "eagle-import") (part "rcl_334_C-USC1206"))
    )
    (comp (ref "C8")
      (value "0.1uF")
      (footprint "eagle-import:C1206")
      (libsource (lib "eagle-import") (part "rcl_334_C-USC1206"))
    )
    (comp (ref "C9")
      (value "F971C475MAAHT3")
      (footprint "eagle-import:CAPPM3216X180N")
      (fields (field (name "MOUSER_PART_NUMBER") "581-F971C475MAAHT3"))
      (libsource (lib "eagle-import") (part "F971C475MAAHT3"))
    )
    (comp (ref "C10")
      (value "F971C475MAAHT3")
      (footprint "eagle-import:CAPPM3216X180N")
      (fields (field (name "MOUSER_PART_NUMBER") "581-F971C475MAAHT3"))
      (libsource (lib "eagle-import") (part "F971C475MAAHT3"))
    )
    (comp (ref "C13")
      (value "0.1uF")
      (footprint "eagle-import:C1206")
      (libsource (lib "eagle-import") (part "rcl_334_C-USC1206"))
    )
    (comp (ref "C14")
      (value "0.1uF")
      (footprint "eagle-import:C1206")
      (libsource (lib "eagle-import") (part "rcl_334_C-USC1206"))
    )
    (comp (ref "C17")
      (value "F971C475MAAHT3")
      (footprint "eagle-import:CAPPM3216X180N")
      (fields (field (name "MOUSER_PART_NUMBER") "581-F971C475MAAHT3"))
      (libsource (lib "eagle-import") (part "F971C475MAAHT3"))
    )
    (comp (ref "C18")
      (value "F971C475MAAHT3")
      (footprint "eagle-import:CAPPM3216X180N")
      (fields (field (name "MOUSER_PART_NUMBER") "581-F971C475MAAHT3"))
      (libsource (lib "eagle-import") (part "F971C475MAAHT3"))
    )
    (comp (ref "C19")
      (value "0.1uF")
      (footprint "eagle-import:C1206")
      (libsource (lib "eagle-import") (part "rcl_334_C-USC1206"))
    )
    (comp (ref "IC3")
      (value "HCPL0531")
      (footprint "eagle-import:SOIC127P594X363-8N")
      (fields (field (name "MOUSER_PART_NUMBER") "512-HCPL0531"))
      (libsource (lib "eagle-import") (part "HCPL0531"))
    )
    (comp (ref "IC4")
      (value "HCPL0531")
      (footprint "eagle-import:SOIC127P594X363-8N")
      (fields (field (name "MOUSER_PART_NUMBER") "512-HCPL0531"))
      (libsource (lib "eagle-import") (part "HCPL0531"))
    )
    (comp (ref "J5")
      (value "TMS-103-02-L-S")
      (footprint "eagle-import:TMS-103-YY-XX-S")
      (fields (field (name "MOUSER_PART_NUMBER") "200-TMS10302LS"))
      (libsource (lib "eagle-import") (part "TMS-103-02-L-S"))
    )
    (comp (ref "J6")
      (value "TMS-103-02-L-S")
      (footprint "eagle-import:TMS-103-YY-XX-S")
      (fields (field (name "MOUSER_PART_NUMBER") "200-TMS10302LS"))
      (libsource (lib "eagle-import") (part "TMS-103-02-L-S"))
    )
    (comp (ref "LED3")
      (value "XZMDKVG55W-4")
      (footprint "eagle-import:LED_KVG55W-4_SLD")
      (fields (field (name "COPYRIGHT") "Copyright (C) 2018 Accelerated Designs. All rights reserved"))
      (libsource (lib "eagle-import") (part "XZMDKVG55W-4"))
    )
    (comp (ref "LED4")
      (value "XZMDKVG55W-4")
      (footprint "eagle-import:LED_KVG55W-4_SLD")
      (fields (field (name "COPYRIGHT") "Copyright (C) 2018 Accelerated Designs. All rights reserved"))
      (libsource (lib "eagle-import") (part "XZMDKVG55W-4"))
    )
    (comp (ref "OC1")
      (value "TPTP08R")
      (footprint "eagle-import:TP08R")
      (libsource (lib "eagle-import") (part "TPTP08R"))
    )
    (comp (ref "OC2")
      (value "TPTP08R")
      (footprint "eagle-import:TP08R")
      (libsource (lib "eagle-import") (part "TPTP08R"))
    )
    (comp (ref "OC3")
      (value "TPTP10R")
      (footprint "eagle-import:TP10R")
      (libsource (lib "eagle-import") (part "TPTP10R"))
    )
    (comp (ref "OC4")
      (value "TPTP10R")
      (footprint "eagle-import:TP10R")
      (libsource (lib "eagle-import") (part "TPTP10R"))
    )
    (comp (ref "R8")
      (value "4605X-101-221LF")
      (footprint "eagle-import:BO_4605X")
      (fields (field (name "MANUFACTURER_PART_NUMBER") "4605X-101-222LF"))
      (libsource (lib "eagle-import") (part "4605X-101-221LF"))
    )
    (comp (ref "R9")
      (value "4605X-101-332LF")
      (footprint "eagle-import:BO_4605X")
      (fields (field (name "MANUFACTURER_PART_NUMBER") "4605X-101-222LF"))
      (libsource (lib "eagle-import") (part "4605X-101-332LF"))
    )
    (comp (ref "U1")
      (value "AD826ARZ")
      (footprint "eagle-import:R_8_ADI")
      (libsource (lib "eagle-import") (part "AD826ARZ"))
    )
    (comp (ref "U2")
      (value "LT1991IMSPBF")
      (footprint "eagle-import:MSOP-10_MS_LIT")
      (fields (field (name "MANUFACTURER_PART_NUMBER") "LT1991IMS#PBF"))
      (libsource (lib "eagle-import") (part "LT1991IMSPBF"))
    )
    (comp (ref "U3")
      (value "LT1991IMSPBF")
      (footprint "eagle-import:MSOP-10_MS_LIT")
      (fields (field (name "MANUFACTURER_PART_NUMBER") "LT1991IMS#PBF"))
      (libsource (lib "eagle-import") (part "LT1991IMSPBF"))
    )
    (comp (ref "U4")
      (value "MCP41HV31-103E/ST")
      (footprint "eagle-import:TSSOP14_MC_MCH")
      (fields (field (name "COPYRIGHT") "Copyright (C) 2018 Accelerated Designs. All rights reserved"))
      (libsource (lib "eagle-import") (part "MCP41HV31-103E/ST"))
    )
    (comp (ref "U5")
      (value "MCP41HV31-103E/ST")
      (footprint "eagle-import:TSSOP14_MC_MCH")
      (fields (field (name "COPYRIGHT") "Copyright (C) 2018 Accelerated Designs. All rights reserved"))
      (libsource (lib "eagle-import") (part "MCP41HV31-103E/ST"))
    )
    (comp (ref "VO1")
      (value "TPTP10R")
      (footprint "eagle-import:TP10R")
      (libsource (lib "eagle-import") (part "TPTP10R"))
    )
    (comp (ref "VO2")
      (value "TPTP10R")
      (footprint "eagle-import:TP10R")
      (libsource (lib "eagle-import") (part "TPTP10R"))
    )
    (comp (ref "VSTIM1")
      (value "TPTP08R")
      (footprint "eagle-import:TP08R")
      (libsource (lib "eagle-import") (part "TPTP08R"))
    )
    (comp (ref "VSTIM2")
      (value "TPTP08R")
      (footprint "eagle-import:TP08R")
      (libsource (lib "eagle-import") (part "TPTP08R"))
    )
    (comp (ref "+5V")
      (value "TPTP10R")
      (footprint "eagle-import:TP10R")
      (libsource (lib "eagle-import") (part "TPTP10R"))
    )
    (comp (ref "+HV")
      (value "TPTP10R")
      (footprint "eagle-import:TP10R")
      (libsource (lib "eagle-import") (part "TPTP10R"))
    )
    (comp (ref "-5V")
      (value "TPTP10R")
      (footprint "eagle-import:TP10R")
      (libsource (lib "eagle-import") (part "TPTP10R"))
    )
    (comp (ref "-HV")
      (value "TPTP10R")
      (footprint "eagle-import:TP10R")
      (libsource (lib "eagle-import") (part "TPTP10R"))
    )
    (comp (ref "3.3V")
      (value "TPTP10R")
      (footprint "eagle-import:TP10R")
      (libsource (lib "eagle-import") (part "TPTP10R"))
    )
    (comp (ref "AGND")
      (value "TPTP10R")
      (footprint "eagle-import:TP10R")
      (libsource (lib "eagle-import") (part "TPTP10R"))
    )
    (comp (ref "C25")
      (value "0.1uF")
      (footprint "eagle-import:C1206")
      (libsource (lib "eagle-import") (part "C-USC1206"))
    )
    (comp (ref "C26")
      (value "1uF")
      (footprint "eagle-import:C0805")
      (libsource (lib "eagle-import") (part "rcl_334_C-USC0805"))
    )
    (comp (ref "C27")
      (value "10uF")
      (footprint "eagle-import:C0805")
      (libsource (lib "eagle-import") (part "rcl_334_C-USC0805"))
    )
    (comp (ref "C28")
      (value "10nF")
      (footprint "eagle-import:C1206")
      (libsource (lib "eagle-import") (part "C-USC1206"))
    )
    (comp (ref "C29")
      (value "47uF")
      (footprint "eagle-import:PANASONIC_D")
      (libsource (lib "eagle-import") (part "0113_47UF"))
    )
    (comp (ref "C30")
      (value "4.7uF")
      (footprint "eagle-import:CAPPM7343X310N")
      (fields
        (field (name "MANUFACTURER_PART_NUMBER") "593D475X9050D2TE3")
        (field (name "MOUSER_PART_NUMBER") "74-593D475X9050D2TE3")
      )
      (libsource (lib "eagle-import") (part "593D475X9050D2TE3"))
    )
    (comp (ref "C31")
      (value "1uF")
      (footprint "eagle-import:C0805")
      (libsource (lib "eagle-import") (part "rcl_334_C-USC0805"))
    )
    (comp (ref "C32")
      (value "1uF")
      (footprint "eagle-import:C0805")
      (libsource (lib "eagle-import") (part "rcl_334_C-USC0805"))
    )
    (comp (ref "C33")
      (value "4.7uF")
      (footprint "eagle-import:CAPPM7343X310N")
      (fields
        (field (name "MANUFACTURER_PART_NUMBER") "593D475X9050D2TE3")
        (field (name "MOUSER_PART_NUMBER") "74-593D475X9050D2TE3")
      )
      (libsource (lib "eagle-import") (part "593D475X9050D2TE3"))
    )
    (comp (ref "C34")
      (value "4.7uF")
      (footprint "eagle-import:CAPPM7343X310N")
      (fields
        (field (name "MANUFACTURER_PART_NUMBER") "593D475X9050D2TE3")
        (field (name "MOUSER_PART_NUMBER") "74-593D475X9050D2TE3")
      )
      (libsource (lib "eagle-import") (part "593D475X9050D2TE3"))
    )
    (comp (ref "D2")
      (value "SS1P3L")
      (footprint "eagle-import:DO220AAL")
      (fields (field (name "PART_NUMBER") "SS1P3L-M3/84A"))
      (libsource (lib "eagle-import") (part "0025_SS1P3L-M3/84A"))
    )
    (comp (ref "D3")
      (value "MSS1P3L-M3/89A")
      (footprint "eagle-import:MICROSMP")
      (libsource (lib "eagle-import") (part "1653_MSS1P3L-M3/89A"))
    )
    (comp (ref "D4")
      (value "LSM115JE3_TR13")
      (footprint "eagle-import:DIOM5436X330N")
      (fields
        (field (name "ARROW_PART_NUMBER") "LSM115JE3/TR13")
        (field (name "MOUSER_PART_NUMBER") "494-LSM115JE3/TR13")
      )
      (libsource (lib "eagle-import") (part "LSM115JE3_TR13"))
    )
    (comp (ref "DGND")
      (value "TPTP10R")
      (footprint "eagle-import:TP10R")
      (libsource (lib "eagle-import") (part "TPTP10R"))
    )
    (comp (ref "IC13")
      (value "TPS73633DBVR")
      (footprint "eagle-import:SOT95P280X145-5N")
      (fields (field (name "MOUSER_PART_NUMBER") "595-TPS73633DBVR"))
      (libsource (lib "eagle-import") (part "TPS73633DBVR"))
    )
    (comp (ref "IC14")
      (value "MIC3975-5.0YMM-TR")
      (footprint "eagle-import:SOP65P490X109-8N")
      (libsource (lib "eagle-import") (part "MIC3975-5.0YMM-TR"))
    )
    (comp (ref "J7")
      (value "CON-SOCJ-2155")
      (footprint "eagle-import:CONSOCJ2155")
      (fields (field (name "MOUSER_PART_NUMBER") "992-CON-SOCJ-2155"))
      (libsource (lib "eagle-import") (part "CON-SOCJ-2155"))
    )
    (comp (ref "L1")
      (value "MH2029-300Y")
      (footprint "eagle-import:0805")
      (fields (field (name "PART_NUMBER") "BLM21PG300SN1D_/_MH2029-300Y"))
      (libsource (lib "eagle-import") (part "0001_BLM21PG300SN1D_/_MH2029-300Y"))
    )
    (comp (ref "PS1")
      (value "NMT0572SC")
      (footprint "eagle-import:NMT1272SC")
      (fields (field (name "MOUSER_PART_NUMBER") "580-NMT0572SC"))
      (libsource (lib "eagle-import") (part "NMT0572SC"))
    )
    (comp (ref "PS2")
      (value "NMT0572SC")
      (footprint "eagle-import:NMT1272SC")
      (fields (field (name "MOUSER_PART_NUMBER") "580-NMT0572SC"))
      (libsource (lib "eagle-import") (part "NMT0572SC"))
    )
    (comp (ref "R32")
      (value "100K")
      (footprint "eagle-import:R1206")
      (libsource (lib "eagle-import") (part "rcl_334_R-US_R1206"))
    )
    (comp (ref "R33")
      (value "470K")
      (footprint "eagle-import:R1206")
      (libsource (lib "eagle-import") (part "rcl_334_R-US_R1206"))
    )
    (comp (ref "S3")
      (value "1101M2S3CQE2")
      (footprint "eagle-import:1000-SERIES(SPDT)")
      (fields (field (name "MOUSER_PART_NUMBER") "611-1101M2S3CQE2"))
      (libsource (lib "eagle-import") (part "1101M2S3CQE2"))
    )
    (comp (ref "U6")
      (value "LTC4412HS6TRMPBF")
      (footprint "eagle-import:TSOT-23_S6_ADI")
      (fields
        (field (name "MANUFACTURER_PART_NUMBER") "LTC4412HS6#TRMPBF")
        (field (name "COPYRIGHT") "Copyright (C) 2018 Accelerated Designs. All rights reserved")
      )
      (libsource (lib "eagle-import") (part "LTC4412HS6TRMPBF"))
    )
    (comp (ref "U7")
      (value "PMV48XP,215TO-236_SOT23_NEX-L")
      (footprint "eagle-import:TO-236_SOT23_NEX-L")
      (fields
        (field (name "MANUFACTURER_PART_NUMBER") "PMV48XP,215")
        (field (name "COPYRIGHT") "Copyright (C) 2018 Accelerated Designs. All rights reserved")
      )
      (libsource (lib "eagle-import") (part "PMV48XP,215TO-236_SOT23_NEX-L"))
    )
    (comp (ref "U8")
      (value "PDME1-S5-D5-S")
      (footprint "eagle-import:CONV_PDME1-S5-D5-S")
      (fields (field (name "MF") "CUI"))
      (libsource (lib "eagle-import") (part "PDME1-S5-D5-S"))
    )
    (comp (ref "VIN5V")
      (value "TPTP10R")
      (footprint "eagle-import:TP10R")
      (libsource (lib "eagle-import") (part "TPTP10R"))
    )
    (comp (ref "C1")
      (value "0.1uF")
      (footprint "eagle-import:C1206")
      (libsource (lib "eagle-import") (part "C-USC1206"))
    )
    (comp (ref "C2")
      (value "F971C475MAAHT3")
      (footprint "eagle-import:CAPPM3216X180N")
      (fields (field (name "MOUSER_PART_NUMBER") "581-F971C475MAAHT3"))
      (libsource (lib "eagle-import") (part "F971C475MAAHT3"))
    )
    (comp (ref "C3")
      (value "0.1uF")
      (footprint "eagle-import:C1206")
      (libsource (lib "eagle-import") (part "C-USC1206"))
    )
    (comp (ref "C4")
      (value "0.1uF")
      (footprint "eagle-import:C1206")
      (libsource (lib "eagle-import") (part "C-USC1206"))
    )
    (comp (ref "C5")
      (value "0.1uF")
      (footprint "eagle-import:C1206")
      (libsource (lib "eagle-import") (part "C-USC1206"))
    )
    (comp (ref "C6")
      (value "10nF")
      (footprint "eagle-import:C1206")
      (libsource (lib "eagle-import") (part "rcl_334_C-USC1206"))
    )
    (comp (ref "CS1")
      (value "TPTP08R")
      (footprint "eagle-import:TP08R")
      (libsource (lib "eagle-import") (part "TPTP08R"))
    )
    (comp (ref "CS2")
      (value "TPTP08R")
      (footprint "eagle-import:TP08R")
      (libsource (lib "eagle-import") (part "TPTP08R"))
    )
    (comp (ref "F1")
      (value "MF-MSMF050-2 500mA")
      (footprint "eagle-import:L1812")
      (fields (field (name "PART_NUMBER") "MF-MSMF050-2"))
      (libsource (lib "eagle-import") (part "0002_MF-MSMF050-2"))
    )
    (comp (ref "IC1")
      (value "DSPIC33FJ256GP506A-I_PT")
      (footprint "eagle-import:QFP50P1200X1200X120-64N")
      (fields
        (field (name "MANUFACTURER_PART_NUMBER") "dsPIC33FJ256GP506A-I/PT")
        (field (name "MOUSER_PART_NUMBER") "579-FJ256GP506A-I/PT")
      )
      (libsource (lib "eagle-import") (part "DSPIC33FJ256GP506A-I_PT"))
    )
    (comp (ref "IC2")
      (value "FT232RL")
      (footprint "eagle-import:SSOP28")
      (libsource (lib "eagle-import") (part "FT232RL"))
    )
    (comp (ref "J1")
      (value "22-27-2051-05")
      (footprint "eagle-import:6410-05")
      (fields (field (name "MF") "MOLEX"))
      (libsource (lib "eagle-import") (part "22-?-0527-2051"))
    )
    (comp (ref "J2")
      (value "47346-0001")
      (footprint "eagle-import:47346-0001")
      (fields (field (name "MOUSER_PART_NUMBER") "538-47346-0001"))
      (libsource (lib "eagle-import") (part "47346-0001"))
    )
    (comp (ref "LED1")
      (value "LEDCHIPLED_1206")
      (footprint "eagle-import:CHIPLED_1206")
      (libsource (lib "eagle-import") (part "LEDCHIPLED_1206"))
    )
    (comp (ref "LED2")
      (value "LEDCHIPLED_1206")
      (footprint "eagle-import:CHIPLED_1206")
      (libsource (lib "eagle-import") (part "LEDCHIPLED_1206"))
    )
    (comp (ref "R1")
      (value "10K")
      (footprint "eagle-import:R1206")
      (libsource (lib "eagle-import") (part "R-US_R1206"))
    )
    (comp (ref "R2")
      (value "470E")
      (footprint "eagle-import:R1206")
      (libsource (lib "eagle-import") (part "R-US_R1206"))
    )
    (comp (ref "R3")
      (value "10K")
      (footprint "eagle-import:R1206")
      (libsource (lib "eagle-import") (part "R-US_R1206"))
    )
    (comp (ref "R4")
      (value "10K")
      (footprint "eagle-import:R1206")
      (libsource (lib "eagle-import") (part "R-US_R1206"))
    )
    (comp (ref "R5")
      (value "330E")
      (footprint "eagle-import:R1206")
      (libsource (lib "eagle-import") (part "R-US_R1206"))
    )
    (comp (ref "R6")
      (value "10K")
      (footprint "eagle-import:R1206")
      (libsource (lib "eagle-import") (part "R-US_R1206"))
    )
    (comp (ref "R7")
      (value "330E")
      (footprint "eagle-import:R1206")
      (libsource (lib "eagle-import") (part "R-US_R1206"))
    )
    (comp (ref "S1")
      (value "SWITCH-MOMENTARY-2SMD")
      (footprint "eagle-import:TACTILE_SWITCH_SMD")
      (libsource (lib "eagle-import") (part "SWITCH-MOMENTARY-2SMD"))
    )
    (comp (ref "SCK")
      (value "TPTP10R")
      (footprint "eagle-import:TP10R")
      (libsource (lib "eagle-import") (part "TPTP10R"))
    )
    (comp (ref "SDI")
      (value "TPTP10R")
      (footprint "eagle-import:TP10R")
      (libsource (lib "eagle-import") (part "TPTP10R"))
    )
    (comp (ref "SDO")
      (value "TPTP10R")
      (footprint "eagle-import:TP10R")
      (libsource (lib "eagle-import") (part "TPTP10R"))
    )
    (comp (ref "TP1")
      (value "DNP")
      (footprint "eagle-import:TP-1.00MM")
      (libsource (lib "eagle-import") (part "TPTP-1.00MM"))
    )
    (comp (ref "TP2")
      (value "DNP")
      (footprint "eagle-import:TP-1.00MM")
      (libsource (lib "eagle-import") (part "TPTP-1.00MM"))
    )
    (comp (ref "TP3")
      (value "DNP")
      (footprint "eagle-import:TP-1.00MM")
      (libsource (lib "eagle-import") (part "TPTP-1.00MM"))
    )
    (comp (ref "TP4")
      (value "DNP")
      (footprint "eagle-import:TP-1.00MM")
      (libsource (lib "eagle-import") (part "TPTP-1.00MM"))
    )
  )
  (nets
    (net (code "1") (name "+3V3") (class "Default")
      (node (ref "3.3V") (pin "TP") (pinfunction "TP_TP") (pintype "input"))
      (node (ref "C19") (pin "1") (pinfunction "1_1") (pintype "passive"))
      (node (ref "C3") (pin "1") (pinfunction "1_1") (pintype "passive"))
      (node (ref "C4") (pin "1") (pinfunction "1_1") (pintype "passive"))
      (node (ref "C5") (pin "1") (pinfunction "1_1") (pintype "passive"))
      (node (ref "IC1") (pin "10") (pinfunction "VDD_1_10") (pintype "bidirectional"))
      (node (ref "IC1") (pin "19") (pinfunction "AVDD_19") (pintype "bidirectional"))
      (node (ref "IC1") (pin "26") (pinfunction "VDD_2_26") (pintype "bidirectional"))
      (node (ref "IC1") (pin "38") (pinfunction "VDD_3_38") (pintype "bidirectional"))
      (node (ref "IC1") (pin "57") (pinfunction "VDD_4_57") (pintype "bidirectional"))
      (node (ref "IC13") (pin "5") (pinfunction "OUT_5") (pintype "bidirectional"))
      (node (ref "J1") (pin "2") (pinfunction "S_2") (pintype "passive"))
      (node (ref "R1") (pin "2") (pinfunction "2_2") (pintype "passive"))
      (node (ref "R17") (pin "2") (pinfunction "2_2") (pintype "passive"))
      (node (ref "R3") (pin "1") (pinfunction "1_1") (pintype "passive"))
      (node (ref "R36") (pin "2") (pinfunction "2_2") (pintype "passive"))
      (node (ref "R37") (pin "2") (pinfunction "2_2") (pintype "passive"))
      (node (ref "R4") (pin "1") (pinfunction "1_1") (pintype "passive"))
      (node (ref "R8") (pin "1") (pinfunction "1_1") (pintype "passive"))
      (node (ref "S2") (pin "3") (pinfunction "A_3") (pintype "bidirectional"))
      (node (ref "U4") (pin "1") (pinfunction "VL_1") (pintype "power_in"))
      (node (ref "U4") (pin "7") (pinfunction "~{SHDN}_7") (pintype "input"))
      (node (ref "U5") (pin "1") (pinfunction "VL_1") (pintype "power_in"))
      (node (ref "U5") (pin "7") (pinfunction "~{SHDN}_7") (pintype "input"))
    )
    (net (code "2") (name "+5V") (class "Default")
      (node (ref "+5V") (pin "TP") (pinfunction "TP_TP") (pintype "input"))
      (node (ref "C10") (pin "1") (pinfunction "+_1") (pintype "bidirectional"))
      (node (ref "C14") (pin "1") (pinfunction "1_1") (pintype "passive"))
      (node (ref "C17") (pin "1") (pinfunction "+_1") (pintype "bidirectional"))
      (node (ref "C21") (pin "1") (pinfunction "1_1") (pintype "passive"))
      (node (ref "C34") (pin "1") (pinfunction "+_1") (pintype "bidirectional"))
      (node (ref "C7") (pin "1") (pinfunction "1_1") (pintype "passive"))
      (node (ref "C8") (pin "1") (pinfunction "1_1") (pintype "passive"))
      (node (ref "IC3") (pin "8") (pinfunction "VCC_8") (pintype "power_in"))
      (node (ref "IC4") (pin "8") (pinfunction "VCC_8") (pintype "power_in"))
      (node (ref "IC6") (pin "6") (pinfunction "VCC_6") (pintype "bidirectional"))
      (node (ref "R9") (pin "1") (pinfunction "1_1") (pintype "passive"))
      (node (ref "U1") (pin "8") (pinfunction "V+_8") (pintype "power_in"))
      (node (ref "U2") (pin "7") (pinfunction "VCC_7") (pintype "power_in"))
      (node (ref "U3") (pin "7") (pinfunction "VCC_7") (pintype "power_in"))
      (node (ref "U4") (pin "14") (pinfunction "V+_14") (pintype "power_in"))
      (node (ref "U5") (pin "14") (pinfunction "V+_14") (pintype "power_in"))
      (node (ref "U8") (pin "6") (pinfunction "+VOUT_6") (pintype "output"))
      (node (ref "U9") (pin "1") (pinfunction "IN_1") (pintype "input"))
    )
    (net (code "3") (name "-5V") (class "Default")
      (node (ref "-5V") (pin "TP") (pinfunction "TP_TP") (pintype "input"))
      (node (ref "C13") (pin "2") (pinfunction "2_2") (pintype "passive"))
      (node (ref "C18") (pin "2") (pinfunction "-_2") (pintype "bidirectional"))
      (node (ref "C33") (pin "2") (pinfunction "-_2") (pintype "bidirectional"))
      (node (ref "C9") (pin "2") (pinfunction "-_2") (pintype "bidirectional"))
      (node (ref "U1") (pin "4") (pinfunction "V-_4") (pintype "power_in"))
      (node (ref "U2") (pin "4") (pinfunction "VEE_4") (pintype "power_in"))
      (node (ref "U3") (pin "4") (pinfunction "VEE_4") (pintype "power_in"))
      (node (ref "U4") (pin "10") (pinfunction "V-_10") (pintype "power_in"))
      (node (ref "U5") (pin "10") (pinfunction "V-_10") (pintype "power_in"))
      (node (ref "U8") (pin "4") (pinfunction "-VOUT_4") (pintype "output"))
    )
    (net (code "4") (name "AD3") (class "Default")
      (node (ref "JP7") (pin "4") (pinfunction "4_4") (pintype "passive"))
    )
    (net (code "5") (name "AD4") (class "Default")
      (node (ref "JP7") (pin "5") (pinfunction "5_5") (pintype "passive"))
    )
    (net (code "6") (name "AD5") (class "Default")
      (node (ref "JP7") (pin "6") (pinfunction "6_6") (pintype "passive"))
    )
    (net (code "7") (name "AD6") (class "Default")
      (node (ref "JP7") (pin "7") (pinfunction "7_7") (pintype "passive"))
    )
    (net (code "8") (name "AD7") (class "Default")
      (node (ref "JP7") (pin "8") (pinfunction "8_8") (pintype "passive"))
    )
    (net (code "9") (name "AD8") (class "Default")
      (node (ref "JP8") (pin "1") (pinfunction "1_1") (pintype "passive"))
    )
    (net (code "10") (name "AD9") (class "Default")
      (node (ref "JP8") (pin "2") (pinfunction "2_2") (pintype "passive"))
    )
    (net (code "11") (name "AD10") (class "Default")
      (node (ref "JP8") (pin "3") (pinfunction "3_3") (pintype "passive"))
    )
    (net (code "12") (name "AD11(TXD3)") (class "Default")
      (node (ref "JP8") (pin "4") (pinfunction "4_4") (pintype "passive"))
    )
    (net (code "13") (name "AGND") (class "Default")
      (node (ref "AGND") (pin "TP") (pinfunction "TP_TP") (pintype "input"))
      (node (ref "C10") (pin "2") (pinfunction "-_2") (pintype "bidirectional"))
      (node (ref "C13") (pin "1") (pinfunction "1_1") (pintype "passive"))
      (node (ref "C14") (pin "2") (pinfunction "2_2") (pintype "passive"))
      (node (ref "C17") (pin "2") (pinfunction "-_2") (pintype "bidirectional"))
      (node (ref "C18") (pin "1") (pinfunction "+_1") (pintype "bidirectional"))
      (node (ref "C21") (pin "2") (pinfunction "2_2") (pintype "passive"))
      (node (ref "C31") (pin "1") (pinfunction "1_1") (pintype "passive"))
      (node (ref "C32") (pin "2") (pinfunction "2_2") (pintype "passive"))
      (node (ref "C33") (pin "1") (pinfunction "+_1") (pintype "bidirectional"))
      (node (ref "C34") (pin "2") (pinfunction "-_2") (pintype "bidirectional"))
      (node (ref "C35") (pin "2") (pinfunction "2_2") (pintype "passive"))
      (node (ref "C36") (pin "2") (pinfunction "2_2") (pintype "passive"))
      (node (ref "C37") (pin "2") (pinfunction "2_2") (pintype "passive"))
      (node (ref "C38") (pin "2") (pinfunction "2_2") (pintype "passive"))
      (node (ref "C7") (pin "2") (pinfunction "2_2") (pintype "passive"))
      (node (ref "C8") (pin "2") (pinfunction "2_2") (pintype "passive"))
      (node (ref "C9") (pin "1") (pinfunction "+_1") (pintype "bidirectional"))
      (node (ref "IC3") (pin "5") (pinfunction "GND_5") (pintype "power_in"))
      (node (ref "IC4") (pin "5") (pinfunction "GND_5") (pintype "power_in"))
      (node (ref "IC5") (pin "2") (pinfunction "-IN_2") (pintype "input"))
      (node (ref "IC6") (pin "1") (pinfunction "IN-_1") (pintype "bidirectional"))
      (node (ref "IC6") (pin "2") (pinfunction "GND_2") (pintype "bidirectional"))
      (node (ref "IC6") (pin "4") (pinfunction "SHDN_4") (pintype "bidirectional"))
      (node (ref "IC8") (pin "2") (pinfunction "-IN_2") (pintype "input"))
      (node (ref "J5") (pin "2") (pinfunction "2_2") (pintype "bidirectional"))
      (node (ref "J6") (pin "2") (pinfunction "2_2") (pintype "bidirectional"))
      (node (ref "PS1") (pin "5") (pinfunction "+VOUT_5") (pintype "bidirectional"))
      (node (ref "PS2") (pin "8") (pinfunction "-VOUT3_8") (pintype "bidirectional"))
      (node (ref "R10") (pin "1") (pinfunction "1_1") (pintype "passive"))
      (node (ref "R25") (pin "2") (pinfunction "2_2") (pintype "passive"))
      (node (ref "U4") (pin "11") (pinfunction "P0B_11") (pintype "bidirectional"))
      (node (ref "U5") (pin "11") (pinfunction "P0B_11") (pintype "bidirectional"))
      (node (ref "U8") (pin "5") (pinfunction "0V_5") (pintype "power_in"))
      (node (ref "U9") (pin "3") (pinfunction "GND_3") (pintype "power_in"))
    )
    (net (code "14") (name "AREF") (class "Default")
      (node (ref "JP3") (pin "8") (pinfunction "8_8") (pintype "passive"))
    )
    (net (code "15") (name "BD+") (class "Default")
      (node (ref "IC2") (pin "15") (pinfunction "USBDP_15") (pintype "bidirectional"))
      (node (ref "J2") (pin "3") (pinfunction "D+_3") (pintype "bidirectional"))
      (node (ref "TP1") (pin "X") (pinfunction "P$1_X") (pintype "passive"))
    )
    (net (code "16") (name "BD-") (class "Default")
      (node (ref "IC2") (pin "16") (pinfunction "USBDM_16") (pintype "bidirectional"))
      (node (ref "J2") (pin "2") (pinfunction "D-_2") (pintype "bidirectional"))
      (node (ref "TP2") (pin "X") (pinfunction "P$1_X") (pintype "passive"))
    )
    (net (code "17") (name "CANRX0") (class "Default")
      (node (ref "JP8") (pin "7") (pinfunction "7_7") (pintype "passive"))
    )
    (net (code "18") (name "CANTX0") (class "Default")
      (node (ref "JP8") (pin "8") (pinfunction "8_8") (pintype "passive"))
    )
    (net (code "19") (name "CH1_EN~{}") (class "Default")
      (node (ref "IC1") (pin "15") (pinfunction "PGEC3/AN1/VREF-/CN3/RB1_15") (pintype "bidirectional"))
      (node (ref "K1") (pin "2") (pinfunction "-_CONTROL_-_SWITCH_#1_2") (pintype "bidirectional"))
    )
    (net (code "20") (name "CH2_EN~{}") (class "Default")
      (node (ref "IC1") (pin "14") (pinfunction "AN2/~{SS1}/CN4/RB2_14") (pintype "bidirectional"))
      (node (ref "K1") (pin "4") (pinfunction "-_CONTROL_-_SWITCH_#2_4") (pintype "bidirectional"))
    )
    (net (code "21") (name "COMM_RET") (class "Default")
      (node (ref "IC6") (pin "8") (pinfunction "IN+_8") (pintype "bidirectional"))
      (node (ref "J3") (pin "2") (pinfunction "2_2") (pintype "passive"))
      (node (ref "J4") (pin "2") (pinfunction "2_2") (pintype "passive"))
      (node (ref "R10") (pin "2") (pinfunction "2_2") (pintype "passive"))
      (node (ref "R16") (pin "2") (pinfunction "2_2") (pintype "passive"))
      (node (ref "R23") (pin "2") (pinfunction "2_2") (pintype "passive"))
    )
    (net (code "22") (name "CS_DIGIPOT1") (class "Default")
      (node (ref "CS1") (pin "TP") (pinfunction "TP_TP") (pintype "input"))
      (node (ref "IC1") (pin "8") (pinfunction "~{SS2}/CN11/RG9_8") (pintype "bidirectional"))
      (node (ref "U5") (pin "3") (pinfunction "~{CS}_3") (pintype "input"))
    )
    (net (code "23") (name "CS_DIGIPOT2") (class "Default")
      (node (ref "CS2") (pin "TP") (pinfunction "TP_TP") (pintype "input"))
      (node (ref "IC1") (pin "18") (pinfunction "PGED1/AN7/RB7_18") (pintype "bidirectional"))
      (node (ref "U4") (pin "3") (pinfunction "~{CS}_3") (pintype "input"))
    )
    (net (code "24") (name "DAC0(CANRX1)") (class "Default")
      (node (ref "JP8") (pin "5") (pinfunction "5_5") (pintype "passive"))
    )
    (net (code "25") (name "DAC1") (class "Default")
      (node (ref "JP8") (pin "6") (pinfunction "6_6") (pintype "passive"))
    )
    (net (code "26") (name "DC_5V") (class "Default")
      (node (ref "C27") (pin "1") (pinfunction "1_1") (pintype "passive"))
      (node (ref "IC14") (pin "4") (pinfunction "OUT_4") (pintype "bidirectional"))
      (node (ref "R32") (pin "1") (pinfunction "1_1") (pintype "passive"))
      (node (ref "U6") (pin "1") (pinfunction "VIN_1") (pintype "power_in"))
      (node (ref "U7") (pin "3") (pinfunction "D_3") (pintype "passive"))
    )
    (net (code "27") (name "EOFF_R~{}") (class "Default")
      (node (ref "IC1") (pin "16") (pinfunction "PGED3/AN0/VREF+/CN2/RB0_16") (pintype "bidirectional"))
      (node (ref "Q8") (pin "1") (pinfunction "B_1") (pintype "bidirectional"))
    )
    (net (code "28") (name "ERR_FLG") (class "Default")
      (node (ref "IC1") (pin "44") (pinfunction "IC3/INT3/RD10_44") (pintype "bidirectional"))
      (node (ref "IC14") (pin "3") (pinfunction "FLG_3") (pintype "bidirectional"))
      (node (ref "R32") (pin "2") (pinfunction "2_2") (pintype "passive"))
    )
    (net (code "29") (name "GND") (class "Default")
      (node (ref "C1") (pin "2") (pinfunction "2_2") (pintype "passive"))
      (node (ref "C19") (pin "2") (pinfunction "2_2") (pintype "passive"))
      (node (ref "C2") (pin "2") (pinfunction "-_2") (pintype "bidirectional"))
      (node (ref "C25") (pin "2") (pinfunction "2_2") (pintype "passive"))
      (node (ref "C26") (pin "2") (pinfunction "2_2") (pintype "passive"))
      (node (ref "C27") (pin "2") (pinfunction "2_2") (pintype "passive"))
      (node (ref "C28") (pin "2") (pinfunction "2_2") (pintype "passive"))
      (node (ref "C29") (pin "-") (pinfunction "-_-") (pintype "passive"))
      (node (ref "C3") (pin "2") (pinfunction "2_2") (pintype "passive"))
      (node (ref "C30") (pin "2") (pinfunction "-_2") (pintype "bidirectional"))
      (node (ref "C4") (pin "2") (pinfunction "2_2") (pintype "passive"))
      (node (ref "C5") (pin "2") (pinfunction "2_2") (pintype "passive"))
      (node (ref "C6") (pin "2") (pinfunction "2_2") (pintype "passive"))
      (node (ref "DGND") (pin "TP") (pinfunction "TP_TP") (pintype "input"))
      (node (ref "IC1") (pin "20") (pinfunction "AVSS_20") (pintype "bidirectional"))
      (node (ref "IC1") (pin "25") (pinfunction "VSS_2_25") (pintype "bidirectional"))
      (node (ref "IC1") (pin "41") (pinfunction "VSS_3_41") (pintype "bidirectional"))
      (node (ref "IC1") (pin "9") (pinfunction "VSS_1_9") (pintype "bidirectional"))
      (node (ref "IC13") (pin "2") (pinfunction "GND_2") (pintype "bidirectional"))
      (node (ref "IC14") (pin "5") (pinfunction "GND_1_5") (pintype "bidirectional"))
      (node (ref "IC14") (pin "6") (pinfunction "GND_2_6") (pintype "bidirectional"))
      (node (ref "IC14") (pin "7") (pinfunction "GND_3_7") (pintype "bidirectional"))
      (node (ref "IC14") (pin "8") (pinfunction "GND_4_8") (pintype "bidirectional"))
      (node (ref "IC2") (pin "18") (pinfunction "GND_18") (pintype "power_in"))
      (node (ref "IC2") (pin "21") (pinfunction "GND_21") (pintype "power_in"))
      (node (ref "IC2") (pin "25") (pinfunction "GND_25") (pintype "power_in"))
      (node (ref "IC2") (pin "26") (pinfunction "TEST_26") (pintype "input"))
      (node (ref "IC2") (pin "7") (pinfunction "GND_7") (pintype "power_in"))
      (node (ref "J1") (pin "3") (pinfunction "S_3") (pintype "passive"))
      (node (ref "J2") (pin "5") (pinfunction "GND_5") (pintype "bidirectional"))
      (node (ref "J7") (pin "2") (pinfunction "2_2") (pintype "bidirectional"))
      (node (ref "J7") (pin "3") (pinfunction "3_3") (pintype "bidirectional"))
      (node (ref "JP3") (pin "7") (pinfunction "7_7") (pintype "passive"))
      (node (ref "JP6") (pin "6") (pinfunction "6_6") (pintype "passive"))
      (node (ref "JP6") (pin "7") (pinfunction "7_7") (pintype "passive"))
      (node (ref "LED5") (pin "C") (pinfunction "C_C") (pintype "passive"))
      (node (ref "LED6") (pin "C") (pinfunction "C_C") (pintype "passive"))
      (node (ref "PS1") (pin "2") (pinfunction "-VIN_2") (pintype "bidirectional"))
      (node (ref "PS2") (pin "2") (pinfunction "-VIN_2") (pintype "bidirectional"))
      (node (ref "Q8") (pin "3") (pinfunction "C_3") (pintype "bidirectional"))
      (node (ref "R25") (pin "1") (pinfunction "1_1") (pintype "passive"))
      (node (ref "S1") (pin "1") (pinfunction "1_1") (pintype "passive"))
      (node (ref "S2") (pin "1") (pinfunction "COM_1") (pintype "bidirectional"))
      (node (ref "TP4") (pin "X") (pinfunction "P$1_X") (pintype "passive"))
      (node (ref "U4") (pin "6") (pinfunction "~{WLAT}_6") (pintype "input"))
      (node (ref "U4") (pin "8") (pinfunction "DGND_8") (pintype "power_in"))
      (node (ref "U5") (pin "6") (pinfunction "~{WLAT}_6") (pintype "input"))
      (node (ref "U5") (pin "8") (pinfunction "DGND_8") (pintype "power_in"))
      (node (ref "U6") (pin "2") (pinfunction "GND_2") (pintype "passive"))
      (node (ref "U6") (pin "3") (pinfunction "CTL_3") (pintype "input"))
      (node (ref "U8") (pin "2") (pinfunction "GND_2") (pintype "power_in"))
    )
    (net (code "30") (name "INT0") (class "Default")
      (node (ref "IC1") (pin "35") (pinfunction "~{U1RTS}/SCK1/INT0/RF6_35") (pintype "bidirectional"))
      (node (ref "R17") (pin "1") (pinfunction "1_1") (pintype "passive"))
      (node (ref "S2") (pin "2") (pinfunction "NO_2") (pintype "bidirectional"))
    )
    (net (code "31") (name "IOUT") (class "Default")
      (node (ref "IC1") (pin "22") (pinfunction "AN9/RB9_22") (pintype "bidirectional"))
      (node (ref "JP7") (pin "1") (pinfunction "1_1") (pintype "passive"))
      (node (ref "R24") (pin "1") (pinfunction "1_1") (pintype "passive"))
    )
    (net (code "32") (name "MASTER-RESET") (class "Default")
      (node (ref "C1") (pin "1") (pinfunction "1_1") (pintype "passive"))
      (node (ref "JP6") (pin "3") (pinfunction "3_3") (pintype "passive"))
      (node (ref "R1") (pin "1") (pinfunction "1_1") (pintype "passive"))
      (node (ref "R2") (pin "1") (pinfunction "1_1") (pintype "passive"))
      (node (ref "S1") (pin "3") (pinfunction "2_3") (pintype "passive"))
    )
    (net (code "33") (name "Net-(C2-+)") (class "Default")
      (node (ref "C2") (pin "1") (pinfunction "+_1") (pintype "bidirectional"))
      (node (ref "IC1") (pin "56") (pinfunction "VCAP_56") (pintype "bidirectional"))
    )
    (net (code "34") (name "Net-(D2-A)") (class "Default")
      (node (ref "D2") (pin "P$2") (pinfunction "A_P$2") (pintype "bidirectional"))
      (node (ref "D3") (pin "A") (pinfunction "A_A") (pintype "passive"))
      (node (ref "L1") (pin "1") (pinfunction "1_1") (pintype "passive"))
    )
    (net (code "35") (name "Net-(D5-A)") (class "Default")
      (node (ref "D5") (pin "2") (pinfunction "A_2") (pintype "bidirectional"))
      (node (ref "JP6") (pin "5") (pinfunction "5_5") (pintype "passive"))
    )
    (net (code "36") (name "Net-(D6-Pad2)") (class "Default")
      (node (ref "D6") (pin "2") (pinfunction "2_2") (pintype "passive"))
      (node (ref "R13") (pin "1") (pinfunction "1_1") (pintype "passive"))
    )
    (net (code "37") (name "Net-(D7-Pad1)") (class "Default")
      (node (ref "D7") (pin "1") (pinfunction "1_1") (pintype "passive"))
      (node (ref "R12") (pin "2") (pinfunction "2_2") (pintype "passive"))
    )
    (net (code "38") (name "Net-(D8-Pad2)") (class "Default")
      (node (ref "D8") (pin "2") (pinfunction "2_2") (pintype "passive"))
      (node (ref "R20") (pin "1") (pinfunction "1_1") (pintype "passive"))
    )
    (net (code "39") (name "Net-(D9-Pad1)") (class "Default")
      (node (ref "D9") (pin "1") (pinfunction "1_1") (pintype "passive"))
      (node (ref "R19") (pin "2") (pinfunction "2_2") (pintype "passive"))
    )
    (net (code "40") (name "Net-(F2-Pad2)") (class "Default")
      (node (ref "F2") (pin "2") (pinfunction "2_2") (pintype "bidirectional"))
      (node (ref "J3") (pin "1") (pinfunction "1_1") (pintype "passive"))
    )
    (net (code "41") (name "Net-(F3-Pad2)") (class "Default")
      (node (ref "F3") (pin "2") (pinfunction "2_2") (pintype "bidirectional"))
      (node (ref "J4") (pin "1") (pinfunction "1_1") (pintype "passive"))
    )
    (net (code "42") (name "Net-(IC2-3V3OUT)") (class "Default")
      (node (ref "IC2") (pin "17") (pinfunction "3V3OUT_17") (pintype "output"))
      (node (ref "IC2") (pin "4") (pinfunction "VCCIO_4") (pintype "power_in"))
    )
    (net (code "43") (name "Net-(IC2-CBUS0)") (class "Default")
      (node (ref "IC2") (pin "23") (pinfunction "CBUS0_23") (pintype "bidirectional"))
      (node (ref "LED2") (pin "C") (pinfunction "C_C") (pintype "passive"))
    )
    (net (code "44") (name "Net-(IC2-CBUS1)") (class "Default")
      (node (ref "IC2") (pin "22") (pinfunction "CBUS1_22") (pintype "bidirectional"))
      (node (ref "LED1") (pin "C") (pinfunction "C_C") (pintype "passive"))
    )
    (net (code "45") (name "Net-(IC2-CBUS3)") (class "Default")
      (node (ref "IC2") (pin "14") (pinfunction "CBUS3_14") (pintype "bidirectional"))
      (node (ref "R6") (pin "1") (pinfunction "1_1") (pintype "passive"))
    )
    (net (code "46") (name "Net-(IC3-V01)") (class "Default")
      (node (ref "IC3") (pin "7") (pinfunction "V01_7") (pintype "bidirectional"))
      (node (ref "R9") (pin "2") (pinfunction "2_2") (pintype "passive"))
      (node (ref "U2") (pin "1") (pinfunction "P1_1") (pintype "input"))
    )
    (net (code "47") (name "Net-(IC3-V02)") (class "Default")
      (node (ref "IC3") (pin "6") (pinfunction "V02_6") (pintype "bidirectional"))
      (node (ref "R9") (pin "3") (pinfunction "3_3") (pintype "passive"))
      (node (ref "U2") (pin "10") (pinfunction "M1_10") (pintype "input"))
    )
    (net (code "48") (name "Net-(IC3-VF1+)") (class "Default")
      (node (ref "IC3") (pin "1") (pinfunction "VF1+_1") (pintype "bidirectional"))
      (node (ref "R8") (pin "3") (pinfunction "3_3") (pintype "passive"))
    )
    (net (code "49") (name "Net-(IC3-VF2+)") (class "Default")
      (node (ref "IC3") (pin "4") (pinfunction "VF2+_4") (pintype "bidirectional"))
      (node (ref "R8") (pin "2") (pinfunction "2_2") (pintype "passive"))
    )
    (net (code "50") (name "Net-(IC4-V01)") (class "Default")
      (node (ref "IC4") (pin "7") (pinfunction "V01_7") (pintype "bidirectional"))
      (node (ref "R9") (pin "4") (pinfunction "4_4") (pintype "passive"))
      (node (ref "U3") (pin "1") (pinfunction "P1_1") (pintype "input"))
    )
    (net (code "51") (name "Net-(IC4-V02)") (class "Default")
      (node (ref "IC4") (pin "6") (pinfunction "V02_6") (pintype "bidirectional"))
      (node (ref "R9") (pin "5") (pinfunction "5_5") (pintype "passive"))
      (node (ref "U3") (pin "10") (pinfunction "M1_10") (pintype "input"))
    )
    (net (code "52") (name "Net-(IC4-VF1+)") (class "Default")
      (node (ref "IC4") (pin "1") (pinfunction "VF1+_1") (pintype "bidirectional"))
      (node (ref "R8") (pin "5") (pinfunction "5_5") (pintype "passive"))
    )
    (net (code "53") (name "Net-(IC4-VF2+)") (class "Default")
      (node (ref "IC4") (pin "4") (pinfunction "VF2+_4") (pintype "bidirectional"))
      (node (ref "R8") (pin "4") (pinfunction "4_4") (pintype "passive"))
    )
    (net (code "54") (name "Net-(IC5-REF_A)") (class "Default")
      (node (ref "IC5") (pin "1") (pinfunction "REF_B_1") (pintype "input"))
      (node (ref "IC5") (pin "5") (pinfunction "REF_A_5") (pintype "input"))
      (node (ref "IC7") (pin "2") (pinfunction "-IN_2") (pintype "input"))
      (node (ref "IC7") (pin "6") (pinfunction "OUT_6") (pintype "output"))
      (node (ref "VF/B1") (pin "TP") (pinfunction "TP_TP") (pintype "input"))
    )
    (net (code "55") (name "Net-(IC5-V+)") (class "Default")
      (node (ref "IC5") (pin "7") (pinfunction "V+_7") (pintype "power_in"))
      (node (ref "IC7") (pin "7") (pinfunction "V+_7") (pintype "bidirectional"))
      (node (ref "Q2") (pin "1") (pinfunction "E_1") (pintype "bidirectional"))
      (node (ref "V1") (pin "TP") (pinfunction "TP_TP") (pintype "input"))
    )
    (net (code "56") (name "Net-(IC5-V-)") (class "Default")
      (node (ref "IC5") (pin "4") (pinfunction "V-_4") (pintype "power_in"))
      (node (ref "IC7") (pin "4") (pinfunction "V-_4") (pintype "bidirectional"))
      (node (ref "Q1") (pin "1") (pinfunction "E_1") (pintype "bidirectional"))
      (node (ref "V2") (pin "TP") (pinfunction "TP_TP") (pintype "input"))
    )
    (net (code "57") (name "Net-(IC5-V_OUT)") (class "Default")
      (node (ref "D6") (pin "1") (pinfunction "1_1") (pintype "passive"))
      (node (ref "D7") (pin "2") (pinfunction "2_2") (pintype "passive"))
      (node (ref "IC5") (pin "6") (pinfunction "V_OUT_6") (pintype "output"))
      (node (ref "R15") (pin "2") (pinfunction "2_2") (pintype "passive"))
    )
    (net (code "58") (name "Net-(IC6-OUT)") (class "Default")
      (node (ref "IC6") (pin "5") (pinfunction "OUT_5") (pintype "bidirectional"))
      (node (ref "R24") (pin "2") (pinfunction "2_2") (pintype "passive"))
    )
    (net (code "59") (name "Net-(IC6-VREF1)") (class "Default")
      (node (ref "1.6V") (pin "TP") (pinfunction "TP_TP") (pintype "input"))
      (node (ref "IC6") (pin "3") (pinfunction "VREF2_3") (pintype "bidirectional"))
      (node (ref "IC6") (pin "7") (pinfunction "VREF1_7") (pintype "bidirectional"))
      (node (ref "U9") (pin "2") (pinfunction "OUT_2") (pintype "output"))
    )
    (net (code "60") (name "Net-(IC7-+IN)") (class "Default")
      (node (ref "F2") (pin "1") (pinfunction "1_1") (pintype "bidirectional"))
      (node (ref "IC7") (pin "3") (pinfunction "+IN_3") (pintype "input"))
      (node (ref "K1") (pin "8") (pinfunction "LOAD_-_SWITCH_#1_2_8") (pintype "bidirectional"))
      (node (ref "R15") (pin "1") (pinfunction "1_1") (pintype "passive"))
    )
    (net (code "61") (name "Net-(IC8-V_OUT)") (class "Default")
      (node (ref "D8") (pin "1") (pinfunction "1_1") (pintype "passive"))
      (node (ref "D9") (pin "2") (pinfunction "2_2") (pintype "passive"))
      (node (ref "IC8") (pin "6") (pinfunction "V_OUT_6") (pintype "output"))
      (node (ref "R22") (pin "2") (pinfunction "2_2") (pintype "passive"))
    )
    (net (code "62") (name "Net-(IC10-+IN)") (class "Default")
      (node (ref "F3") (pin "1") (pinfunction "1_1") (pintype "bidirectional"))
      (node (ref "IC10") (pin "3") (pinfunction "+IN_3") (pintype "input"))
      (node (ref "K1") (pin "6") (pinfunction "LOAD_-_SWITCH_#2_2_6") (pintype "bidirectional"))
      (node (ref "R22") (pin "1") (pinfunction "1_1") (pintype "passive"))
    )
    (net (code "63") (name "Net-(IC10--IN)") (class "Default")
      (node (ref "IC10") (pin "2") (pinfunction "-IN_2") (pintype "input"))
      (node (ref "IC10") (pin "6") (pinfunction "OUT_6") (pintype "output"))
      (node (ref "IC8") (pin "1") (pinfunction "REF_B_1") (pintype "input"))
      (node (ref "IC8") (pin "5") (pinfunction "REF_A_5") (pintype "input"))
      (node (ref "VF/B2") (pin "TP") (pinfunction "TP_TP") (pintype "input"))
    )
    (net (code "64") (name "Net-(IC10-V+)") (class "Default")
      (node (ref "IC10") (pin "7") (pinfunction "V+_7") (pintype "bidirectional"))
      (node (ref "IC8") (pin "7") (pinfunction "V+_7") (pintype "power_in"))
      (node (ref "Q4") (pin "1") (pinfunction "E_1") (pintype "bidirectional"))
      (node (ref "V3") (pin "TP") (pinfunction "TP_TP") (pintype "input"))
    )
    (net (code "65") (name "Net-(IC10-V-)") (class "Default")
      (node (ref "IC10") (pin "4") (pinfunction "V-_4") (pintype "bidirectional"))
      (node (ref "IC8") (pin "4") (pinfunction "V-_4") (pintype "power_in"))
      (node (ref "Q3") (pin "1") (pinfunction "E_1") (pintype "bidirectional"))
      (node (ref "V4") (pin "TP") (pinfunction "TP_TP") (pintype "input"))
    )
    (net (code "66") (name "Net-(IC13-NR{slash}FB)") (class "Default")
      (node (ref "C28") (pin "1") (pinfunction "1_1") (pintype "passive"))
      (node (ref "IC13") (pin "4") (pinfunction "NR/FB_4") (pintype "bidirectional"))
    )
    (net (code "67") (name "Net-(K1-+_CONTROL_-_SWITCH_#1)") (class "Default")
      (node (ref "K1") (pin "1") (pinfunction "+_CONTROL_-_SWITCH_#1_1") (pintype "bidirectional"))
      (node (ref "R37") (pin "1") (pinfunction "1_1") (pintype "passive"))
    )
    (net (code "68") (name "Net-(K1-+_CONTROL_-_SWITCH_#2)") (class "Default")
      (node (ref "K1") (pin "3") (pinfunction "+_CONTROL_-_SWITCH_#2_3") (pintype "bidirectional"))
      (node (ref "R36") (pin "1") (pinfunction "1_1") (pintype "passive"))
    )
    (net (code "69") (name "Net-(K1-LOAD_-_SWITCH_#1_1)") (class "Default")
      (node (ref "K1") (pin "7") (pinfunction "LOAD_-_SWITCH_#1_1_7") (pintype "bidirectional"))
      (node (ref "R16") (pin "1") (pinfunction "1_1") (pintype "passive"))
    )
    (net (code "70") (name "Net-(K1-LOAD_-_SWITCH_#2_1)") (class "Default")
      (node (ref "K1") (pin "5") (pinfunction "LOAD_-_SWITCH_#2_1_5") (pintype "bidirectional"))
      (node (ref "R23") (pin "1") (pinfunction "1_1") (pintype "passive"))
    )
    (net (code "71") (name "Net-(LED1-PadA)") (class "Default")
      (node (ref "LED1") (pin "A") (pinfunction "A_A") (pintype "passive"))
      (node (ref "R7") (pin "1") (pinfunction "1_1") (pintype "passive"))
    )
    (net (code "72") (name "Net-(LED2-PadA)") (class "Default")
      (node (ref "LED2") (pin "A") (pinfunction "A_A") (pintype "passive"))
      (node (ref "R5") (pin "1") (pinfunction "1_1") (pintype "passive"))
    )
    (net (code "73") (name "Net-(LED5-PadA)") (class "Default")
      (node (ref "LED5") (pin "A") (pinfunction "A_A") (pintype "passive"))
      (node (ref "R26") (pin "1") (pinfunction "1_1") (pintype "passive"))
    )
    (net (code "74") (name "Net-(LED6-PadA)") (class "Default")
      (node (ref "LED6") (pin "A") (pinfunction "A_A") (pintype "passive"))
      (node (ref "R27") (pin "1") (pinfunction "1_1") (pintype "passive"))
    )
    (net (code "75") (name "Net-(PS1-+VIN)") (class "Default")
      (node (ref "PS1") (pin "1") (pinfunction "+VIN_1") (pintype "bidirectional"))
      (node (ref "PS2") (pin "1") (pinfunction "+VIN_1") (pintype "bidirectional"))
      (node (ref "S3") (pin "1") (pinfunction "1_1") (pintype "bidirectional"))
      (node (ref "S3") (pin "2") (pinfunction "2_2") (pintype "bidirectional"))
    )
    (net (code "76") (name "Net-(Q1-B)") (class "Default")
      (node (ref "C39") (pin "2") (pinfunction "2_2") (pintype "passive"))
      (node (ref "Q1") (pin "3") (pinfunction "B_3") (pintype "bidirectional"))
      (node (ref "R11") (pin "2") (pinfunction "2_2") (pintype "passive"))
      (node (ref "R12") (pin "1") (pinfunction "1_1") (pintype "passive"))
    )
    (net (code "77") (name "Net-(Q2-B)") (class "Default")
      (node (ref "C39") (pin "1") (pinfunction "1_1") (pintype "passive"))
      (node (ref "Q2") (pin "3") (pinfunction "B_3") (pintype "bidirectional"))
      (node (ref "R13") (pin "2") (pinfunction "2_2") (pintype "passive"))
      (node (ref "R14") (pin "1") (pinfunction "1_1") (pintype "passive"))
    )
    (net (code "78") (name "Net-(Q3-B)") (class "Default")
      (node (ref "C40") (pin "2") (pinfunction "2_2") (pintype "passive"))
      (node (ref "Q3") (pin "3") (pinfunction "B_3") (pintype "bidirectional"))
      (node (ref "R18") (pin "2") (pinfunction "2_2") (pintype "passive"))
      (node (ref "R19") (pin "1") (pinfunction "1_1") (pintype "passive"))
    )
    (net (code "79") (name "Net-(Q4-B)") (class "Default")
      (node (ref "C40") (pin "1") (pinfunction "1_1") (pintype "passive"))
      (node (ref "Q4") (pin "3") (pinfunction "B_3") (pintype "bidirectional"))
      (node (ref "R20") (pin "2") (pinfunction "2_2") (pintype "passive"))
      (node (ref "R21") (pin "1") (pinfunction "1_1") (pintype "passive"))
    )
    (net (code "80") (name "Net-(Q8-E)") (class "Default")
      (node (ref "Q8") (pin "2") (pinfunction "E_2") (pintype "bidirectional"))
      (node (ref "R34") (pin "1") (pinfunction "1_1") (pintype "passive"))
    )
    (net (code "81") (name "Net-(S2-K)") (class "Default")
      (node (ref "R34") (pin "2") (pinfunction "2_2") (pintype "passive"))
      (node (ref "S2") (pin "4") (pinfunction "K_4") (pintype "bidirectional"))
    )
    (net (code "82") (name "Net-(U1-IN1+)") (class "Default")
      (node (ref "U1") (pin "3") (pinfunction "IN1+_3") (pintype "passive"))
      (node (ref "U5") (pin "12") (pinfunction "P0W_12") (pintype "bidirectional"))
    )
    (net (code "83") (name "Net-(U1-IN2+)") (class "Default")
      (node (ref "U1") (pin "5") (pinfunction "IN2+_5") (pintype "passive"))
      (node (ref "U4") (pin "12") (pinfunction "P0W_12") (pintype "bidirectional"))
    )
    (net (code "84") (name "Net-(U2-OUT)") (class "Default")
      (node (ref "LED4") (pin "1") (pinfunction "1_1") (pintype "passive"))
      (node (ref "U2") (pin "6") (pinfunction "OUT_6") (pintype "output"))
      (node (ref "VO2") (pin "TP") (pinfunction "TP_TP") (pintype "input"))
    )
    (net (code "85") (name "Net-(U2-P3)") (class "Default")
      (node (ref "J6") (pin "1") (pinfunction "1_1") (pintype "bidirectional"))
      (node (ref "U2") (pin "2") (pinfunction "P3_2") (pintype "input"))
    )
    (net (code "86") (name "Net-(U2-REF)") (class "Default")
      (node (ref "J6") (pin "3") (pinfunction "3_3") (pintype "bidirectional"))
      (node (ref "U2") (pin "5") (pinfunction "REF_5") (pintype "input"))
    )
    (net (code "87") (name "Net-(U3-OUT)") (class "Default")
      (node (ref "LED3") (pin "1") (pinfunction "1_1") (pintype "passive"))
      (node (ref "U3") (pin "6") (pinfunction "OUT_6") (pintype "output"))
      (node (ref "VO1") (pin "TP") (pinfunction "TP_TP") (pintype "input"))
    )
    (net (code "88") (name "Net-(U3-P3)") (class "Default")
      (node (ref "J5") (pin "1") (pinfunction "1_1") (pintype "bidirectional"))
      (node (ref "U3") (pin "2") (pinfunction "P3_2") (pintype "input"))
    )
    (net (code "89") (name "Net-(U3-REF)") (class "Default")
      (node (ref "J5") (pin "3") (pinfunction "3_3") (pintype "bidirectional"))
      (node (ref "U3") (pin "5") (pinfunction "REF_5") (pintype "input"))
    )
    (net (code "90") (name "Net-(U4-P0A)") (class "Default")
      (node (ref "LED4") (pin "2") (pinfunction "2_2") (pintype "passive"))
      (node (ref "U4") (pin "13") (pinfunction "P0A_13") (pintype "bidirectional"))
    )
    (net (code "91") (name "Net-(U5-P0A)") (class "Default")
      (node (ref "LED3") (pin "2") (pinfunction "2_2") (pintype "passive"))
      (node (ref "U5") (pin "13") (pinfunction "P0A_13") (pintype "bidirectional"))
    )
    (net (code "92") (name "Net-(U6-GATE)") (class "Default")
      (node (ref "U6") (pin "5") (pinfunction "GATE_5") (pintype "passive"))
      (node (ref "U7") (pin "1") (pinfunction "G_1") (pintype "passive"))
    )
    (net (code "93") (name "OC1") (class "Default")
      (node (ref "IC1") (pin "46") (pinfunction "OC1/RD0_46") (pintype "bidirectional"))
      (node (ref "IC4") (pin "2") (pinfunction "VF1-_2") (pintype "bidirectional"))
      (node (ref "OC1") (pin "TP") (pinfunction "TP_TP") (pintype "input"))
    )
    (net (code "94") (name "OC2") (class "Default")
      (node (ref "IC1") (pin "49") (pinfunction "OC2/RD1_49") (pintype "bidirectional"))
      (node (ref "IC4") (pin "3") (pinfunction "VF2-_3") (pintype "bidirectional"))
      (node (ref "OC2") (pin "TP") (pinfunction "TP_TP") (pintype "input"))
    )
    (net (code "95") (name "OC3") (class "Default")
      (node (ref "IC1") (pin "50") (pinfunction "OC3/RD2_50") (pintype "bidirectional"))
      (node (ref "IC3") (pin "2") (pinfunction "VF1-_2") (pintype "bidirectional"))
      (node (ref "OC3") (pin "TP") (pinfunction "TP_TP") (pintype "input"))
    )
    (net (code "96") (name "OC4") (class "Default")
      (node (ref "IC1") (pin "51") (pinfunction "OC4/RD3_51") (pintype "bidirectional"))
      (node (ref "IC3") (pin "3") (pinfunction "VF2-_3") (pintype "bidirectional"))
      (node (ref "OC4") (pin "TP") (pinfunction "TP_TP") (pintype "input"))
    )
    (net (code "97") (name "PGC_2") (class "Default")
      (node (ref "IC1") (pin "48") (pinfunction "PGEC2/SOSCO/T1CK/CN0/RC14_48") (pintype "bidirectional"))
      (node (ref "J1") (pin "5") (pinfunction "S_5") (pintype "passive"))
    )
    (net (code "98") (name "PGD_2") (class "Default")
      (node (ref "IC1") (pin "47") (pinfunction "PGED2/SOSCI/T4CK/CN1/RC13_47") (pintype "bidirectional"))
      (node (ref "J1") (pin "4") (pinfunction "S_4") (pintype "passive"))
    )
    (net (code "99") (name "PWM2") (class "Default")
      (node (ref "JP4") (pin "3") (pinfunction "3_3") (pintype "passive"))
    )
    (net (code "100") (name "PWM3") (class "Default")
      (node (ref "JP4") (pin "4") (pinfunction "4_4") (pintype "passive"))
    )
    (net (code "101") (name "PWM5") (class "Default")
      (node (ref "JP4") (pin "6") (pinfunction "6_6") (pintype "passive"))
    )
    (net (code "102") (name "PWM6") (class "Default")
      (node (ref "JP4") (pin "7") (pinfunction "7_7") (pintype "passive"))
    )
    (net (code "103") (name "PWM7") (class "Default")
      (node (ref "JP4") (pin "8") (pinfunction "8_8") (pintype "passive"))
    )
    (net (code "104") (name "PWM8") (class "Default")
      (node (ref "JP3") (pin "1") (pinfunction "1_1") (pintype "passive"))
    )
    (net (code "105") (name "PWM9") (class "Default")
      (node (ref "IC1") (pin "43") (pinfunction "IC2/~{U1CTS}/INT2/RD9_43") (pintype "bidirectional"))
      (node (ref "JP3") (pin "2") (pinfunction "2_2") (pintype "passive"))
      (node (ref "R26") (pin "2") (pinfunction "2_2") (pintype "passive"))
    )
    (net (code "106") (name "PWM10") (class "Default")
      (node (ref "IC1") (pin "42") (pinfunction "IC1/INT1/RD8_42") (pintype "bidirectional"))
      (node (ref "JP3") (pin "3") (pinfunction "3_3") (pintype "passive"))
      (node (ref "R27") (pin "2") (pinfunction "2_2") (pintype "passive"))
    )
    (net (code "107") (name "PWM11") (class "Default")
      (node (ref "JP3") (pin "4") (pinfunction "4_4") (pintype "passive"))
    )
    (net (code "108") (name "PWM12") (class "Default")
      (node (ref "JP3") (pin "5") (pinfunction "5_5") (pintype "passive"))
    )
    (net (code "109") (name "PWM13") (class "Default")
      (node (ref "JP3") (pin "6") (pinfunction "6_6") (pintype "passive"))
    )
    (net (code "110") (name "RESET~{}") (class "Default")
      (node (ref "IC1") (pin "7") (pinfunction "~{MCLR}_7") (pintype "bidirectional"))
      (node (ref "J1") (pin "1") (pinfunction "S_1") (pintype "passive"))
      (node (ref "R2") (pin "2") (pinfunction "2_2") (pintype "passive"))
    )
    (net (code "111") (name "RX") (class "Default")
      (node (ref "JP4") (pin "1") (pinfunction "1_1") (pintype "passive"))
    )
    (net (code "112") (name "RXD0") (class "Default")
      (node (ref "JP5") (pin "2") (pinfunction "2_2") (pintype "passive"))
    )
    (net (code "113") (name "RXD1") (class "Default")
      (node (ref "JP5") (pin "4") (pinfunction "4_4") (pintype "passive"))
    )
    (net (code "114") (name "RXD2") (class "Default")
      (node (ref "JP5") (pin "6") (pinfunction "6_6") (pintype "passive"))
    )
    (net (code "115") (name "RX_1") (class "Default")
      (node (ref "IC1") (pin "34") (pinfunction "U1RX/SDI1/RF2_34") (pintype "bidirectional"))
      (node (ref "IC2") (pin "1") (pinfunction "TXD_1") (pintype "output"))
    )
    (net (code "116") (name "SCK2") (class "Default")
      (node (ref "IC1") (pin "4") (pinfunction "SCK2/CN8/RG6_4") (pintype "bidirectional"))
      (node (ref "SCK") (pin "TP") (pinfunction "TP_TP") (pintype "input"))
      (node (ref "U4") (pin "2") (pinfunction "SCK_2") (pintype "input"))
      (node (ref "U5") (pin "2") (pinfunction "SCK_2") (pintype "input"))
    )
    (net (code "117") (name "SCL0-3") (class "Default")
      (node (ref "JP5") (pin "8") (pinfunction "8_8") (pintype "passive"))
    )
    (net (code "118") (name "SCL1") (class "Default")
      (node (ref "IC1") (pin "37") (pinfunction "SCL1/RG2_37") (pintype "bidirectional"))
      (node (ref "JP3") (pin "10") (pinfunction "10_10") (pintype "passive"))
      (node (ref "R4") (pin "2") (pinfunction "2_2") (pintype "passive"))
    )
    (net (code "119") (name "SDA0-3") (class "Default")
      (node (ref "JP5") (pin "7") (pinfunction "7_7") (pintype "passive"))
    )
    (net (code "120") (name "SDA1") (class "Default")
      (node (ref "IC1") (pin "36") (pinfunction "SDA1/RG3_36") (pintype "bidirectional"))
      (node (ref "JP3") (pin "9") (pinfunction "9_9") (pintype "passive"))
      (node (ref "R3") (pin "2") (pinfunction "2_2") (pintype "passive"))
    )
    (net (code "121") (name "SDI2") (class "Default")
      (node (ref "IC1") (pin "5") (pinfunction "SDI2/CN9/RG7_5") (pintype "bidirectional"))
      (node (ref "SDI") (pin "TP") (pinfunction "TP_TP") (pintype "input"))
      (node (ref "U4") (pin "5") (pinfunction "SDO_5") (pintype "output"))
      (node (ref "U5") (pin "5") (pinfunction "SDO_5") (pintype "output"))
    )
    (net (code "122") (name "SDO2") (class "Default")
      (node (ref "IC1") (pin "6") (pinfunction "SDO2/CN10/RG8_6") (pintype "bidirectional"))
      (node (ref "SDO") (pin "TP") (pinfunction "TP_TP") (pintype "input"))
      (node (ref "U4") (pin "4") (pinfunction "SDI_4") (pintype "input"))
      (node (ref "U5") (pin "4") (pinfunction "SDI_4") (pintype "input"))
    )
    (net (code "123") (name "SS1{slash}PWM4") (class "Default")
      (node (ref "JP4") (pin "5") (pinfunction "5_5") (pintype "passive"))
    )
    (net (code "124") (name "SUPPLY_STATUS") (class "Default")
      (node (ref "IC1") (pin "45") (pinfunction "IC4/INT4/RD11_45") (pintype "bidirectional"))
      (node (ref "R33") (pin "2") (pinfunction "2_2") (pintype "passive"))
      (node (ref "U6") (pin "4") (pinfunction "STAT_4") (pintype "output"))
    )
    (net (code "125") (name "TX") (class "Default")
      (node (ref "JP4") (pin "2") (pinfunction "2_2") (pintype "passive"))
    )
    (net (code "126") (name "TXD0") (class "Default")
      (node (ref "JP5") (pin "1") (pinfunction "1_1") (pintype "passive"))
    )
    (net (code "127") (name "TXD1") (class "Default")
      (node (ref "JP5") (pin "3") (pinfunction "3_3") (pintype "passive"))
    )
    (net (code "128") (name "TXD2") (class "Default")
      (node (ref "JP5") (pin "5") (pinfunction "5_5") (pintype "passive"))
    )
    (net (code "129") (name "TX_1") (class "Default")
      (node (ref "IC1") (pin "33") (pinfunction "U1TX/SDO1/RF3_33") (pintype "bidirectional"))
      (node (ref "IC2") (pin "5") (pinfunction "RXD_5") (pintype "input"))
    )
    (net (code "130") (name "USB_5V") (class "Default")
      (node (ref "C6") (pin "1") (pinfunction "1_1") (pintype "passive"))
      (node (ref "D4") (pin "2") (pinfunction "A_2") (pintype "bidirectional"))
      (node (ref "F1") (pin "1") (pinfunction "1_1") (pintype "passive"))
      (node (ref "IC2") (pin "20") (pinfunction "VCC_20") (pintype "power_in"))
      (node (ref "R5") (pin "2") (pinfunction "2_2") (pintype "passive"))
      (node (ref "R6") (pin "2") (pinfunction "2_2") (pintype "passive"))
      (node (ref "R7") (pin "2") (pinfunction "2_2") (pintype "passive"))
    )
    (net (code "131") (name "VCC") (class "Default")
      (node (ref "+HV") (pin "TP") (pinfunction "TP_TP") (pintype "input"))
      (node (ref "C32") (pin "1") (pinfunction "1_1") (pintype "passive"))
      (node (ref "C35") (pin "1") (pinfunction "1_1") (pintype "passive"))
      (node (ref "C37") (pin "1") (pinfunction "1_1") (pintype "passive"))
      (node (ref "PS2") (pin "5") (pinfunction "+VOUT_5") (pintype "bidirectional"))
      (node (ref "Q2") (pin "2") (pinfunction "C_2") (pintype "bidirectional"))
      (node (ref "Q4") (pin "2") (pinfunction "C_2") (pintype "bidirectional"))
      (node (ref "R14") (pin "2") (pinfunction "2_2") (pintype "passive"))
      (node (ref "R21") (pin "2") (pinfunction "2_2") (pintype "passive"))
    )
    (net (code "132") (name "VIN") (class "Default")
      (node (ref "C26") (pin "1") (pinfunction "1_1") (pintype "passive"))
      (node (ref "D2") (pin "P$1") (pinfunction "K_P$1") (pintype "bidirectional"))
      (node (ref "D3") (pin "K") (pinfunction "C_K") (pintype "passive"))
      (node (ref "IC14") (pin "1") (pinfunction "EN_1") (pintype "bidirectional"))
      (node (ref "IC14") (pin "2") (pinfunction "IN_2") (pintype "bidirectional"))
      (node (ref "JP6") (pin "8") (pinfunction "8_8") (pintype "passive"))
    )
    (net (code "133") (name "VIN+") (class "Default")
      (node (ref "J7") (pin "1") (pinfunction "1_1") (pintype "bidirectional"))
      (node (ref "L1") (pin "2") (pinfunction "2_2") (pintype "passive"))
    )
    (net (code "134") (name "VIN_5V") (class "Default")
      (node (ref "C25") (pin "1") (pinfunction "1_1") (pintype "passive"))
      (node (ref "C29") (pin "+") (pinfunction "+_+") (pintype "passive"))
      (node (ref "C30") (pin "1") (pinfunction "+_1") (pintype "bidirectional"))
      (node (ref "D4") (pin "1") (pinfunction "K_1") (pintype "bidirectional"))
      (node (ref "D5") (pin "1") (pinfunction "K_1") (pintype "bidirectional"))
      (node (ref "IC13") (pin "1") (pinfunction "IN_1") (pintype "bidirectional"))
      (node (ref "IC13") (pin "3") (pinfunction "EN_3") (pintype "bidirectional"))
      (node (ref "R33") (pin "1") (pinfunction "1_1") (pintype "passive"))
      (node (ref "S3") (pin "3") (pinfunction "3_3") (pintype "bidirectional"))
      (node (ref "U6") (pin "6") (pinfunction "SENSE_6") (pintype "input"))
      (node (ref "U7") (pin "2") (pinfunction "S_2") (pintype "passive"))
      (node (ref "U8") (pin "1") (pinfunction "VIN_1") (pintype "input"))
      (node (ref "VIN5V") (pin "TP") (pinfunction "TP_TP") (pintype "input"))
    )
    (net (code "135") (name "VSS") (class "Default")
      (node (ref "-HV") (pin "TP") (pinfunction "TP_TP") (pintype "input"))
      (node (ref "C31") (pin "2") (pinfunction "2_2") (pintype "passive"))
      (node (ref "C36") (pin "1") (pinfunction "1_1") (pintype "passive"))
      (node (ref "C38") (pin "1") (pinfunction "1_1") (pintype "passive"))
      (node (ref "PS1") (pin "8") (pinfunction "-VOUT3_8") (pintype "bidirectional"))
      (node (ref "Q1") (pin "2") (pinfunction "C_2") (pintype "bidirectional"))
      (node (ref "Q3") (pin "2") (pinfunction "C_2") (pintype "bidirectional"))
      (node (ref "R11") (pin "1") (pinfunction "1_1") (pintype "passive"))
      (node (ref "R18") (pin "1") (pinfunction "1_1") (pintype "passive"))
    )
    (net (code "136") (name "VSTIM1") (class "Default")
      (node (ref "IC5") (pin "3") (pinfunction "+IN_3") (pintype "input"))
      (node (ref "U1") (pin "1") (pinfunction "OUT1_1") (pintype "passive"))
      (node (ref "U1") (pin "2") (pinfunction "IN1-_2") (pintype "passive"))
      (node (ref "VSTIM1") (pin "TP") (pinfunction "TP_TP") (pintype "input"))
    )
    (net (code "137") (name "VSTIM2") (class "Default")
      (node (ref "IC8") (pin "3") (pinfunction "+IN_3") (pintype "input"))
      (node (ref "U1") (pin "6") (pinfunction "IN2-_6") (pintype "passive"))
      (node (ref "U1") (pin "7") (pinfunction "OUT2_7") (pintype "passive"))
      (node (ref "VSTIM2") (pin "TP") (pinfunction "TP_TP") (pintype "input"))
    )
    (net (code "138") (name "XVCC") (class "Default")
      (node (ref "F1") (pin "2") (pinfunction "2_2") (pintype "passive"))
      (node (ref "J2") (pin "1") (pinfunction "VBUS_1") (pintype "bidirectional"))
      (node (ref "TP3") (pin "X") (pinfunction "P$1_X") (pintype "passive"))
    )
    (net (code "139") (name "unconnected-(IC1-AN3{slash}CN5{slash}RB3-Pad13)") (class "Default")
      (node (ref "IC1") (pin "13") (pinfunction "AN3/CN5/RB3_13") (pintype "bidirectional"))
    )
    (net (code "140") (name "unconnected-(IC1-AN4{slash}IC7{slash}CN6{slash}RB4-Pad12)") (class "Default")
      (node (ref "IC1") (pin "12") (pinfunction "AN4/IC7/CN6/RB4_12") (pintype "bidirectional"))
    )
    (net (code "141") (name "unconnected-(IC1-AN5{slash}IC8{slash}CN7{slash}RB5-Pad11)") (class "Default")
      (node (ref "IC1") (pin "11") (pinfunction "AN5/IC8/CN7/RB5_11") (pintype "bidirectional"))
    )
    (net (code "142") (name "unconnected-(IC1-AN15{slash}OCFB{slash}CN12{slash}RB15-Pad30)") (class "Default")
      (node (ref "IC1") (pin "30") (pinfunction "AN15/OCFB/CN12/RB15_30") (pintype "bidirectional"))
    )
    (net (code "143") (name "unconnected-(IC1-AN16{slash}T2CK{slash}T7CK{slash}RC1-Pad2)") (class "Default")
      (node (ref "IC1") (pin "2") (pinfunction "AN16/T2CK/T7CK/RC1_2") (pintype "bidirectional"))
    )
    (net (code "144") (name "unconnected-(IC1-AN17{slash}T3CK{slash}T6CK{slash}RC2-Pad3)") (class "Default")
      (node (ref "IC1") (pin "3") (pinfunction "AN17/T3CK/T6CK/RC2_3") (pintype "bidirectional"))
    )
    (net (code "145") (name "unconnected-(IC1-C1RX{slash}RF0-Pad58)") (class "Default")
      (node (ref "IC1") (pin "58") (pinfunction "C1RX/RF0_58") (pintype "bidirectional"))
    )
    (net (code "146") (name "unconnected-(IC1-C1TX{slash}RF1-Pad59)") (class "Default")
      (node (ref "IC1") (pin "59") (pinfunction "C1TX/RF1_59") (pintype "bidirectional"))
    )
    (net (code "147") (name "unconnected-(IC1-COFS{slash}RG15-Pad1)") (class "Default")
      (node (ref "IC1") (pin "1") (pinfunction "COFS/RG15_1") (pintype "bidirectional"))
    )
    (net (code "148") (name "unconnected-(IC1-CSCK{slash}RG14-Pad62)") (class "Default")
      (node (ref "IC1") (pin "62") (pinfunction "CSCK/RG14_62") (pintype "bidirectional"))
    )
    (net (code "149") (name "unconnected-(IC1-CSDI{slash}RG12-Pad63)") (class "Default")
      (node (ref "IC1") (pin "63") (pinfunction "CSDI/RG12_63") (pintype "bidirectional"))
    )
    (net (code "150") (name "unconnected-(IC1-CSDO{slash}RG13-Pad64)") (class "Default")
      (node (ref "IC1") (pin "64") (pinfunction "CSDO/RG13_64") (pintype "bidirectional"))
    )
    (net (code "151") (name "unconnected-(IC1-OC5{slash}IC5{slash}CN13{slash}RD4-Pad52)") (class "Default")
      (node (ref "IC1") (pin "52") (pinfunction "OC5/IC5/CN13/RD4_52") (pintype "bidirectional"))
    )
    (net (code "152") (name "unconnected-(IC1-OC6{slash}IC6{slash}CN14{slash}RD5-Pad53)") (class "Default")
      (node (ref "IC1") (pin "53") (pinfunction "OC6/IC6/CN14/RD5_53") (pintype "bidirectional"))
    )
    (net (code "153") (name "unconnected-(IC1-OC7{slash}CN15{slash}RD6-Pad54)") (class "Default")
      (node (ref "IC1") (pin "54") (pinfunction "OC7/CN15/RD6_54") (pintype "bidirectional"))
    )
    (net (code "154") (name "unconnected-(IC1-OC8{slash}CN16{slash}RD7-Pad55)") (class "Default")
      (node (ref "IC1") (pin "55") (pinfunction "OC8/CN16/RD7_55") (pintype "bidirectional"))
    )
    (net (code "155") (name "unconnected-(IC1-OSC1{slash}CLKIN{slash}RC12-Pad39)") (class "Default")
      (node (ref "IC1") (pin "39") (pinfunction "OSC1/CLKIN/RC12_39") (pintype "bidirectional"))
    )
    (net (code "156") (name "unconnected-(IC1-OSC2{slash}CLKO{slash}RC15-Pad40)") (class "Default")
      (node (ref "IC1") (pin "40") (pinfunction "OSC2/CLKO/RC15_40") (pintype "bidirectional"))
    )
    (net (code "157") (name "unconnected-(IC1-PGEC1{slash}AN6{slash}OCFA{slash}RB6-Pad17)") (class "Default")
      (node (ref "IC1") (pin "17") (pinfunction "PGEC1/AN6/OCFA/RB6_17") (pintype "bidirectional"))
    )
    (net (code "158") (name "unconnected-(IC1-RG0-Pad61)") (class "Default")
      (node (ref "IC1") (pin "61") (pinfunction "RG0_61") (pintype "bidirectional"))
    )
    (net (code "159") (name "unconnected-(IC1-RG1-Pad60)") (class "Default")
      (node (ref "IC1") (pin "60") (pinfunction "RG1_60") (pintype "bidirectional"))
    )
    (net (code "160") (name "unconnected-(IC1-TCK{slash}AN12{slash}RB12-Pad27)") (class "Default")
      (node (ref "IC1") (pin "27") (pinfunction "TCK/AN12/RB12_27") (pintype "bidirectional"))
    )
    (net (code "161") (name "unconnected-(IC1-TDI{slash}AN13{slash}RB13-Pad28)") (class "Default")
      (node (ref "IC1") (pin "28") (pinfunction "TDI/AN13/RB13_28") (pintype "bidirectional"))
    )
    (net (code "162") (name "unconnected-(IC1-TDO{slash}AN11{slash}RB11-Pad24)") (class "Default")
      (node (ref "IC1") (pin "24") (pinfunction "TDO/AN11/RB11_24") (pintype "bidirectional"))
    )
    (net (code "163") (name "unconnected-(IC1-TMS{slash}AN10{slash}RB10-Pad23)") (class "Default")
      (node (ref "IC1") (pin "23") (pinfunction "TMS/AN10/RB10_23") (pintype "bidirectional"))
    )
    (net (code "164") (name "unconnected-(IC1-U2RX{slash}SDA2{slash}CN17{slash}RF4-Pad31)") (class "Default")
      (node (ref "IC1") (pin "31") (pinfunction "U2RX/SDA2/CN17/RF4_31") (pintype "bidirectional"))
    )
    (net (code "165") (name "unconnected-(IC1-U2TX{slash}SCL2{slash}CN18{slash}RF5-Pad32)") (class "Default")
      (node (ref "IC1") (pin "32") (pinfunction "U2TX/SCL2/CN18/RF5_32") (pintype "bidirectional"))
    )
    (net (code "166") (name "unconnected-(IC1-~{U2CTS}{slash}AN8{slash}RB8-Pad21)") (class "Default")
      (node (ref "IC1") (pin "21") (pinfunction "~{U2CTS}/AN8/RB8_21") (pintype "bidirectional"))
    )
    (net (code "167") (name "unconnected-(IC1-~{U2RTS}{slash}AN14{slash}RB14-Pad29)") (class "Default")
      (node (ref "IC1") (pin "29") (pinfunction "~{U2RTS}/AN14/RB14_29") (pintype "bidirectional"))
    )
    (net (code "168") (name "unconnected-(IC2-CBUS2-Pad13)") (class "Default")
      (node (ref "IC2") (pin "13") (pinfunction "CBUS2_13") (pintype "bidirectional"))
    )
    (net (code "169") (name "unconnected-(IC2-CBUS4-Pad12)") (class "Default")
      (node (ref "IC2") (pin "12") (pinfunction "CBUS4_12") (pintype "bidirectional"))
    )
    (net (code "170") (name "unconnected-(IC2-OSCI-Pad27)") (class "Default")
      (node (ref "IC2") (pin "27") (pinfunction "OSCI_27") (pintype "input"))
    )
    (net (code "171") (name "unconnected-(IC2-OSCO-Pad28)") (class "Default")
      (node (ref "IC2") (pin "28") (pinfunction "OSCO_28") (pintype "output"))
    )
    (net (code "172") (name "unconnected-(IC2-~{CTS}-Pad11)") (class "Default")
      (node (ref "IC2") (pin "11") (pinfunction "~{CTS}_11") (pintype "input"))
    )
    (net (code "173") (name "unconnected-(IC2-~{DCD}-Pad10)") (class "Default")
      (node (ref "IC2") (pin "10") (pinfunction "~{DCD}_10") (pintype "input"))
    )
    (net (code "174") (name "unconnected-(IC2-~{DSR}-Pad9)") (class "Default")
      (node (ref "IC2") (pin "9") (pinfunction "~{DSR}_9") (pintype "input"))
    )
    (net (code "175") (name "unconnected-(IC2-~{DTR}-Pad2)") (class "Default")
      (node (ref "IC2") (pin "2") (pinfunction "~{DTR}_2") (pintype "output"))
    )
    (net (code "176") (name "unconnected-(IC2-~{RESET}-Pad19)") (class "Default")
      (node (ref "IC2") (pin "19") (pinfunction "~{RESET}_19") (pintype "input"))
    )
    (net (code "177") (name "unconnected-(IC2-~{RI}-Pad6)") (class "Default")
      (node (ref "IC2") (pin "6") (pinfunction "~{RI}_6") (pintype "input"))
    )
    (net (code "178") (name "unconnected-(IC2-~{RTS}-Pad3)") (class "Default")
      (node (ref "IC2") (pin "3") (pinfunction "~{RTS}_3") (pintype "output"))
    )
    (net (code "179") (name "unconnected-(IC5-NC-Pad8)") (class "Default")
      (node (ref "IC5") (pin "8") (pinfunction "NC_8") (pintype "no_connect"))
    )
    (net (code "180") (name "unconnected-(IC7-NC-Pad1)") (class "Default")
      (node (ref "IC7") (pin "1") (pinfunction "NC_1") (pintype "no_connect"))
    )
    (net (code "181") (name "unconnected-(IC7-NC_1-Pad5)") (class "Default")
      (node (ref "IC7") (pin "5") (pinfunction "NC_1_5") (pintype "bidirectional"))
    )
    (net (code "182") (name "unconnected-(IC7-NC_2-Pad8)") (class "Default")
      (node (ref "IC7") (pin "8") (pinfunction "NC_2_8") (pintype "bidirectional"))
    )
    (net (code "183") (name "unconnected-(IC8-NC-Pad8)") (class "Default")
      (node (ref "IC8") (pin "8") (pinfunction "NC_8") (pintype "no_connect"))
    )
    (net (code "184") (name "unconnected-(IC10-NC-Pad1)") (class "Default")
      (node (ref "IC10") (pin "1") (pinfunction "NC_1") (pintype "no_connect"))
    )
    (net (code "185") (name "unconnected-(IC10-NC_1-Pad5)") (class "Default")
      (node (ref "IC10") (pin "5") (pinfunction "NC_1_5") (pintype "bidirectional"))
    )
    (net (code "186") (name "unconnected-(IC10-NC_2-Pad8)") (class "Default")
      (node (ref "IC10") (pin "8") (pinfunction "NC_2_8") (pintype "bidirectional"))
    )
    (net (code "187") (name "unconnected-(J2-ID-Pad4)") (class "Default")
      (node (ref "J2") (pin "4") (pinfunction "ID_4") (pintype "bidirectional"))
    )
    (net (code "188") (name "unconnected-(J3-Pad3)") (class "Default")
      (node (ref "J3") (pin "3") (pinfunction "3_3") (pintype "passive"))
    )
    (net (code "189") (name "unconnected-(J4-Pad3)") (class "Default")
      (node (ref "J4") (pin "3") (pinfunction "3_3") (pintype "passive"))
    )
    (net (code "190") (name "unconnected-(JP6-Pad1)") (class "Default")
      (node (ref "JP6") (pin "1") (pinfunction "1_1") (pintype "passive"))
    )
    (net (code "191") (name "unconnected-(JP6-Pad2)") (class "Default")
      (node (ref "JP6") (pin "2") (pinfunction "2_2") (pintype "passive"))
    )
    (net (code "192") (name "unconnected-(JP6-Pad4)") (class "Default")
      (node (ref "JP6") (pin "4") (pinfunction "4_4") (pintype "passive"))
    )
    (net (code "193") (name "unconnected-(JP7-Pad2)") (class "Default")
      (node (ref "JP7") (pin "2") (pinfunction "2_2") (pintype "passive"))
    )
    (net (code "194") (name "unconnected-(JP7-Pad3)") (class "Default")
      (node (ref "JP7") (pin "3") (pinfunction "3_3") (pintype "passive"))
    )
    (net (code "195") (name "unconnected-(PS1--VOUT1-Pad6)") (class "Default")
      (node (ref "PS1") (pin "6") (pinfunction "-VOUT1_6") (pintype "bidirectional"))
    )
    (net (code "196") (name "unconnected-(PS1--VOUT2-Pad7)") (class "Default")
      (node (ref "PS1") (pin "7") (pinfunction "-VOUT2_7") (pintype "bidirectional"))
    )
    (net (code "197") (name "unconnected-(PS2--VOUT1-Pad6)") (class "Default")
      (node (ref "PS2") (pin "6") (pinfunction "-VOUT1_6") (pintype "bidirectional"))
    )
    (net (code "198") (name "unconnected-(PS2--VOUT2-Pad7)") (class "Default")
      (node (ref "PS2") (pin "7") (pinfunction "-VOUT2_7") (pintype "bidirectional"))
    )
    (net (code "199") (name "unconnected-(U2-M3-Pad9)") (class "Default")
      (node (ref "U2") (pin "9") (pinfunction "M3_9") (pintype "input"))
    )
    (net (code "200") (name "unconnected-(U2-M9-Pad8)") (class "Default")
      (node (ref "U2") (pin "8") (pinfunction "M9_8") (pintype "input"))
    )
    (net (code "201") (name "unconnected-(U2-P9-Pad3)") (class "Default")
      (node (ref "U2") (pin "3") (pinfunction "P9_3") (pintype "input"))
    )
    (net (code "202") (name "unconnected-(U3-M3-Pad9)") (class "Default")
      (node (ref "U3") (pin "9") (pinfunction "M3_9") (pintype "input"))
    )
    (net (code "203") (name "unconnected-(U3-M9-Pad8)") (class "Default")
      (node (ref "U3") (pin "8") (pinfunction "M9_8") (pintype "input"))
    )
    (net (code "204") (name "unconnected-(U3-P9-Pad3)") (class "Default")
      (node (ref "U3") (pin "3") (pinfunction "P9_3") (pintype "input"))
    )
    (net (code "205") (name "unconnected-(U4-NC-Pad9)") (class "Default")
      (node (ref "U4") (pin "9") (pinfunction "NC_9") (pintype "no_connect"))
    )
    (net (code "206") (name "unconnected-(U5-NC-Pad9)") (class "Default")
      (node (ref "U5") (pin "9") (pinfunction "NC_9") (pintype "no_connect"))
    )
  )
)
